# MAX86176_WRIST_EVKIT_D.net
KiCad netlist of a schematic drawn in EAGLE
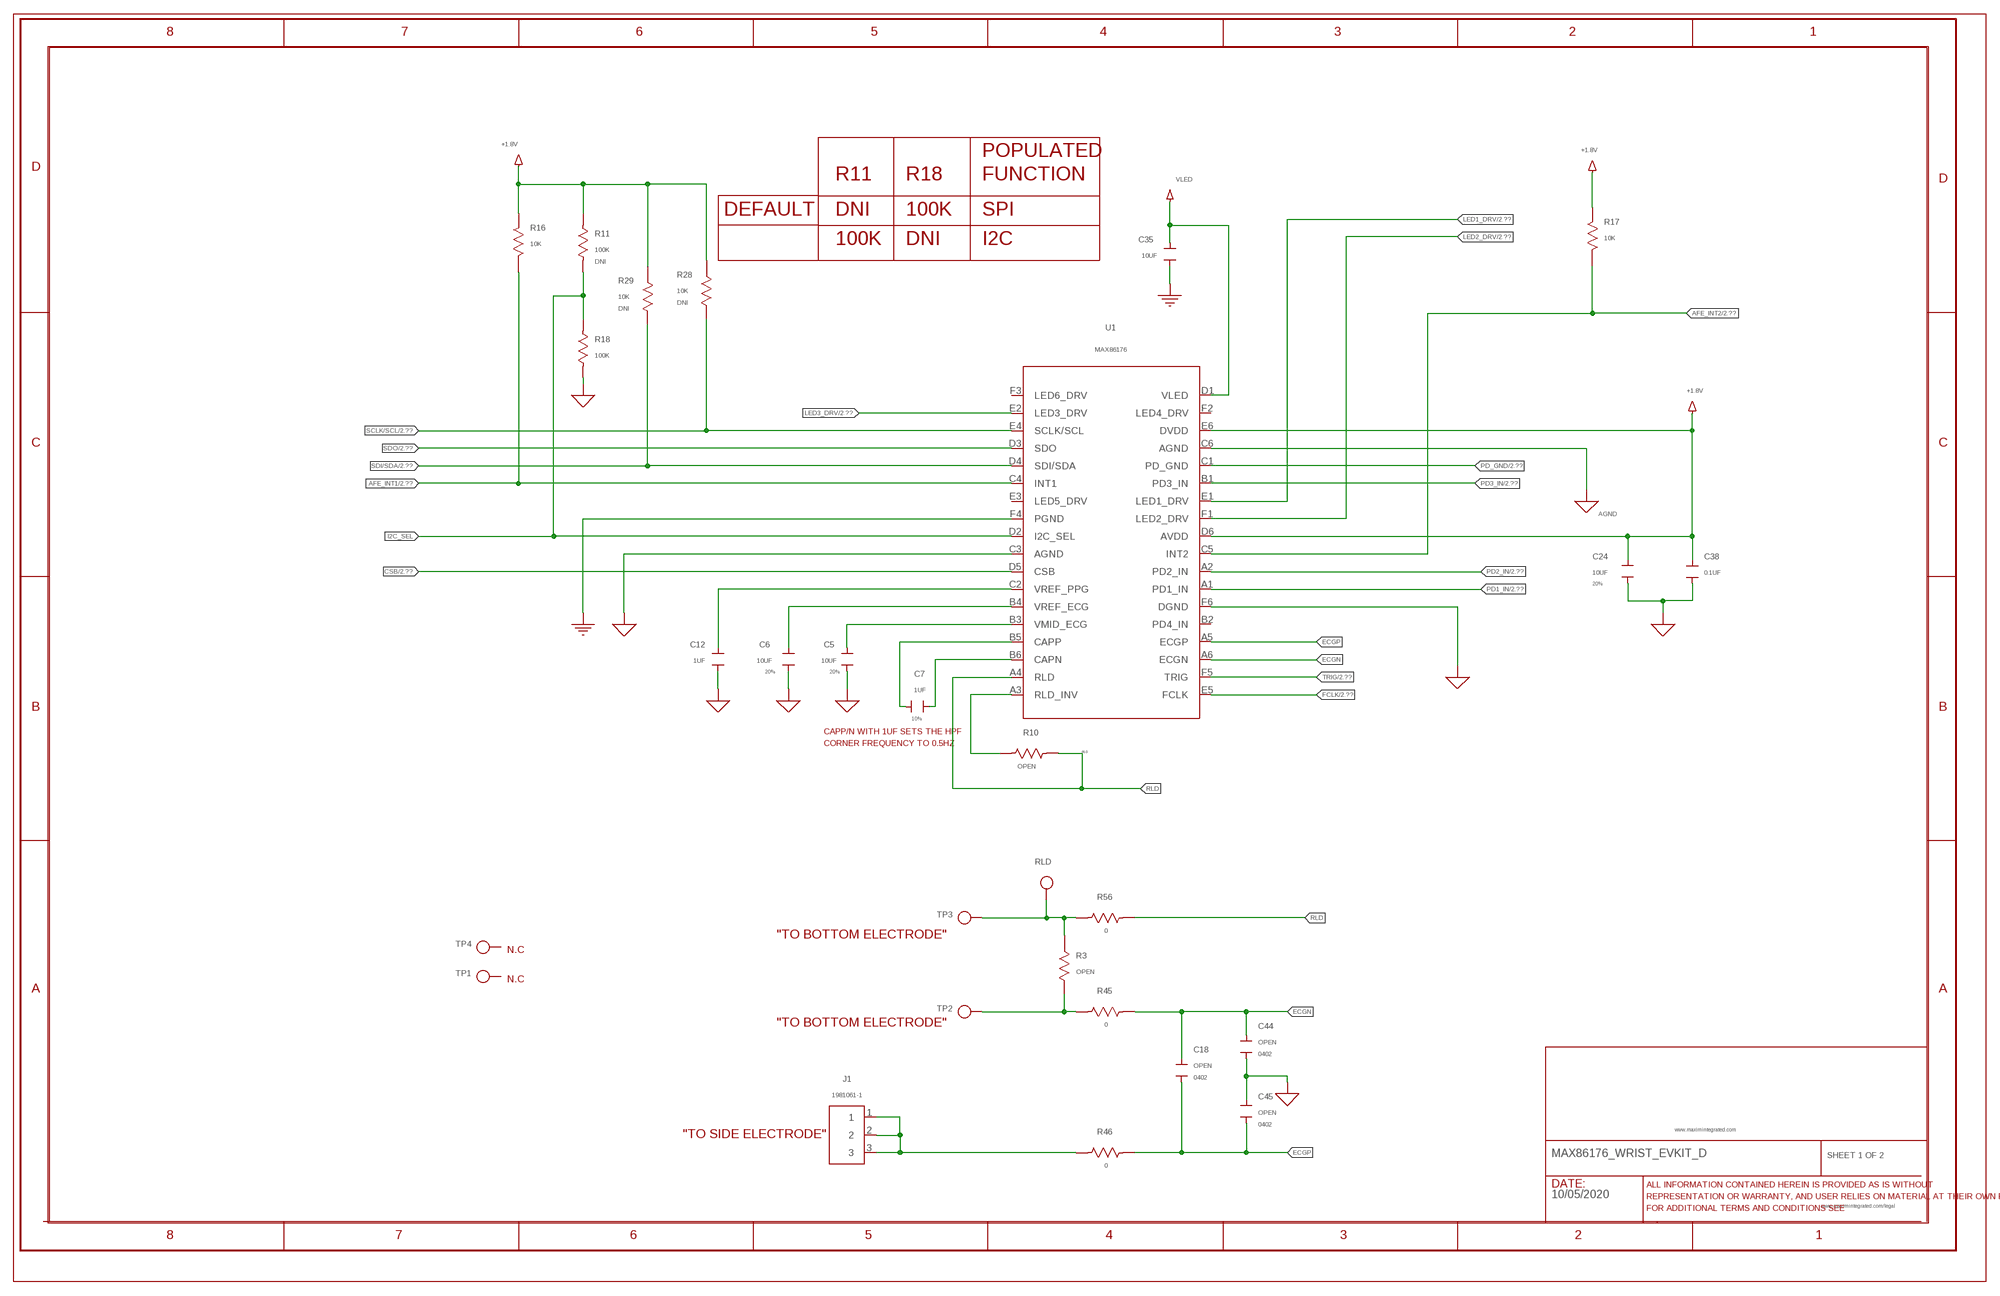
[diagram p0: schematic, sheet 1]
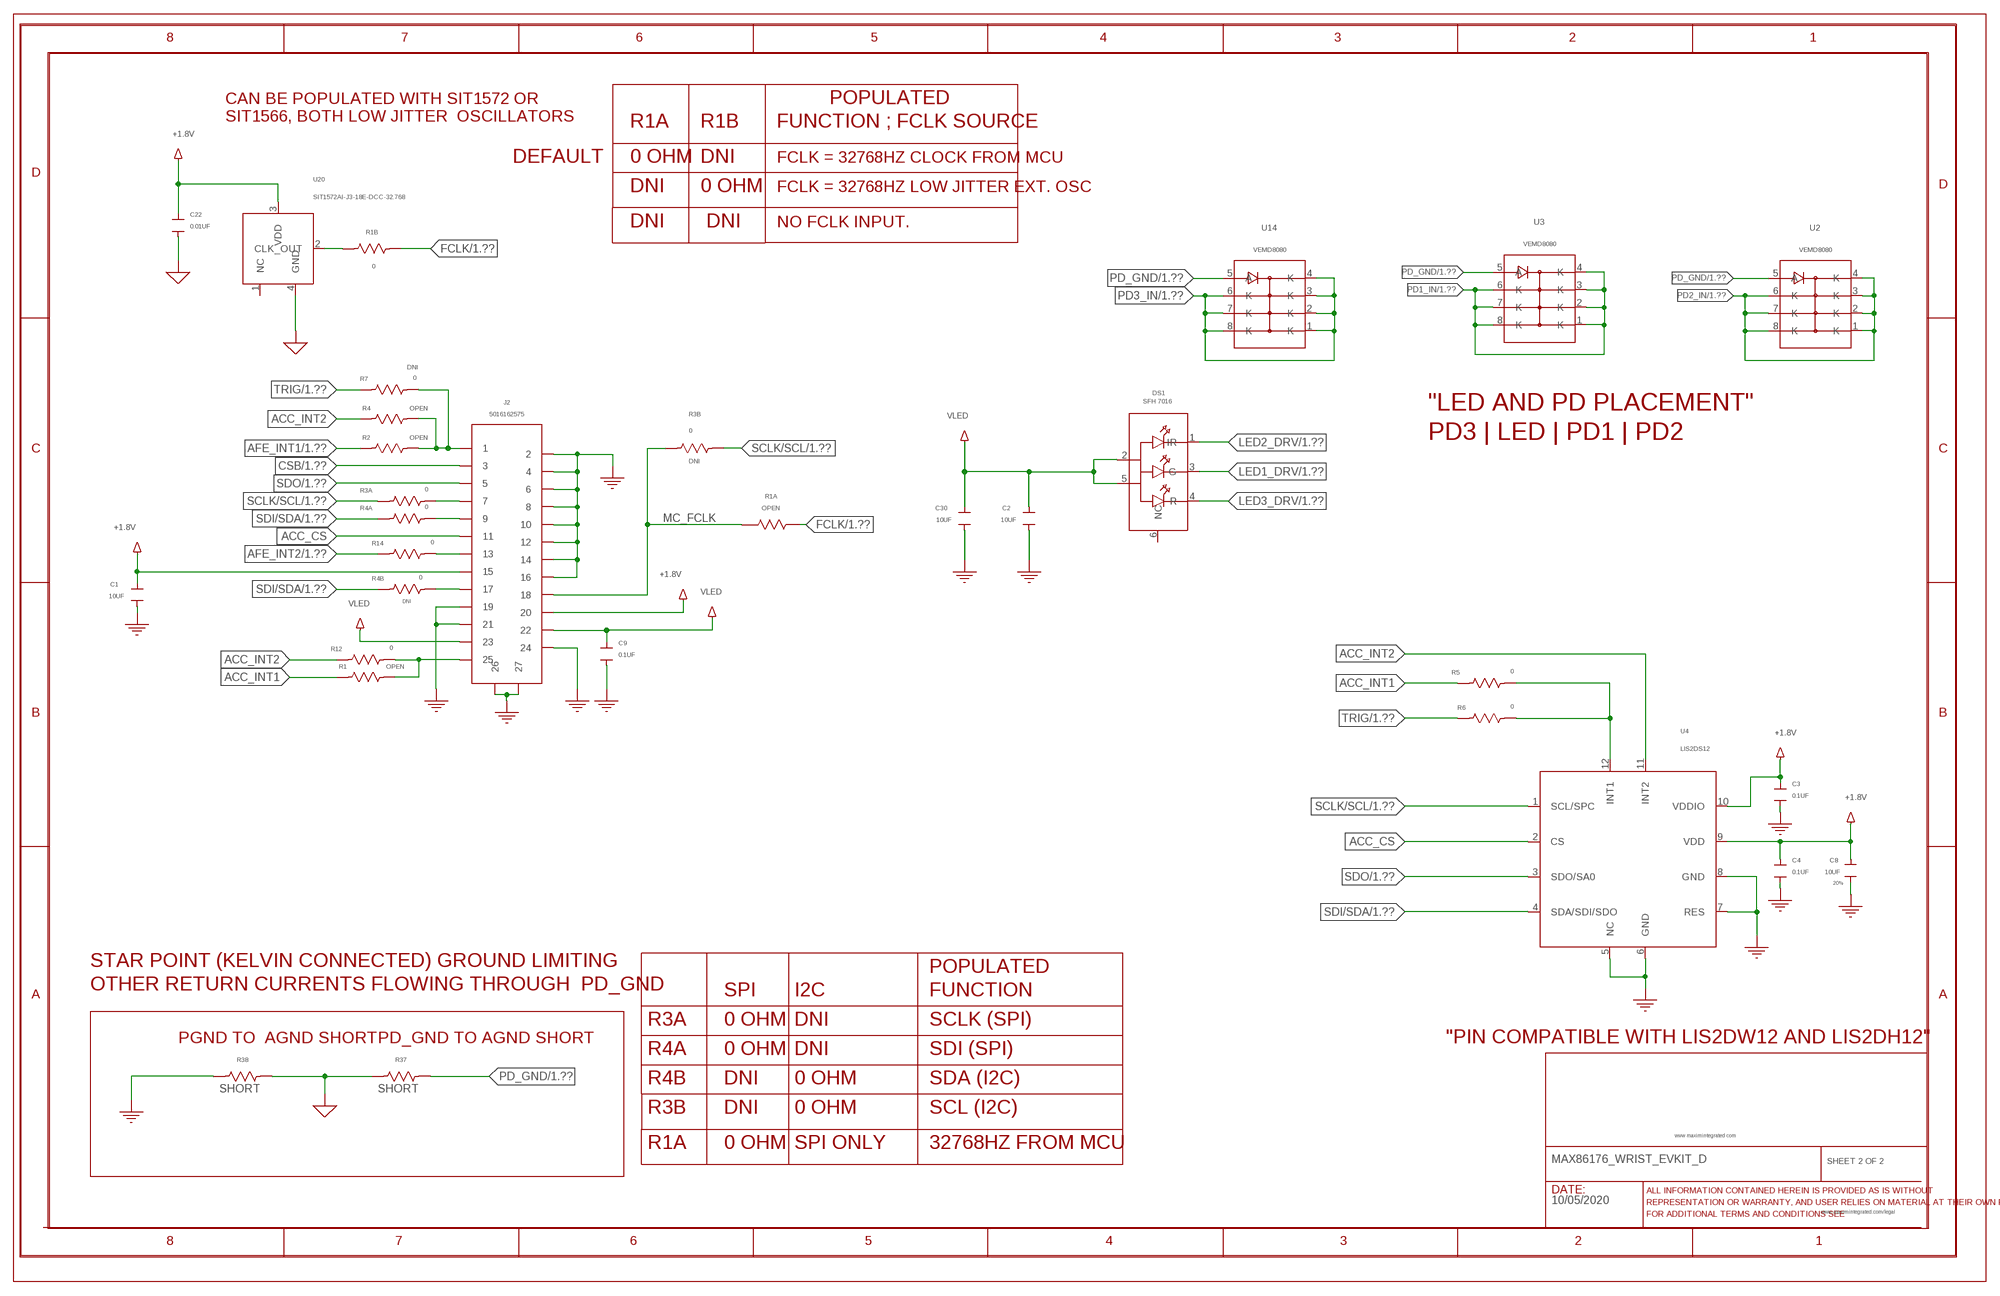
[diagram p1: schematic, sheet 2]

(export (version "E")
  (design (tool "Eeschema 10.0.6"))
  (components
    (comp (ref "C5")
      (value "10UF")
      (footprint "eagle-import:0402")
      (description "CAP: SMT (0402): 10UF: 20%: 10V: X5R: CERAMIC")
      (fields
        (field (name "CAP") "1.00E-05")
        (field (name "CASE") "SMT (0402)")
        (field (name "MANUFACTURER") "MURATA:MURATA:AVX:SAMSUNG")
        (field (name "MATERIAL_TYPE") "CERAMIC CHIP")
        (field (name "MAXINV") "20-0010U-BA12")
        (field (name "MFG_PART_NUMBER") "GRM155R61A106ME44:GRM155R61A106ME11:0402ZD106MAT2A:CL05A106MP5NUNC")
        (field (name "ORIGINALSYMBOLORIGIN") "(-50,50)")
        (field (name "PACK_TYPE") "0402CAP")
        (field (name "PHYS_PAGE") "1")
        (field (name "REFLOW") "-")
        (field (name "TEMP_RANGE") "-55 DEGC TO +85 DEGC")
        (field (name "TOLERANCE") "20%")
        (field (name "VER") "1")
        (field (name "VLOG_PARAM01") "CAP:INTEGER")
        (field (name "VOLTAGE_RATING") "10V")
      )
      (libsource (lib "eagle-import") (part "CAP_NP#1CAP_NP#1_1"))
    )
    (comp (ref "C6")
      (value "10UF")
      (footprint "eagle-import:0402")
      (description "CAP: SMT (0402): 10UF: 20%: 10V: X5R: CERAMIC")
      (fields
        (field (name "CAP") "1.00E-05")
        (field (name "CASE") "SMT (0402)")
        (field (name "MANUFACTURER") "MURATA:MURATA:AVX:SAMSUNG")
        (field (name "MATERIAL_TYPE") "CERAMIC CHIP")
        (field (name "MAXINV") "20-0010U-BA12")
        (field (name "MFG_PART_NUMBER") "GRM155R61A106ME44:GRM155R61A106ME11:0402ZD106MAT2A:CL05A106MP5NUNC")
        (field (name "ORIGINALSYMBOLORIGIN") "(-50,50)")
        (field (name "PACK_TYPE") "0402CAP")
        (field (name "PHYS_PAGE") "1")
        (field (name "REFLOW") "-")
        (field (name "TEMP_RANGE") "-55 DEGC TO +85 DEGC")
        (field (name "TOLERANCE") "20%")
        (field (name "VER") "1")
        (field (name "VLOG_PARAM01") "CAP:INTEGER")
        (field (name "VOLTAGE_RATING") "10V")
      )
      (libsource (lib "eagle-import") (part "CAP_NP#1CAP_NP#1_1"))
    )
    (comp (ref "C7")
      (value "1UF")
      (footprint "eagle-import:0603")
      (description "CAP: SMT (0603): 1UF: 10%: 25V: X7R: CERAMIC")
      (fields
        (field (name "CAP") "1.00E-06")
        (field (name "CASE") "SMT (0603)")
        (field (name "MANUFACTURER") "MURATA:TAIYO YUDEN:AVX:TAIYO YUDEN")
        (field (name "MATERIAL_TYPE") "CERAMIC CHIP")
        (field (name "MAXINV") "20-0001U-P6")
        (field (name "MFG_PART_NUMBER") "GRM188R71E105KA12:CGA3E1X7R1E105K:TMK107B7105KA:06033C105KAT2A:GCM188R71E105KA64:C1608X7R1E105K080AE:CGA3E1X7R1E105K080AC")
        (field (name "ORIGINALSYMBOLORIGIN") "(-50,50)")
        (field (name "PACK_TYPE") "0603CAP")
        (field (name "PHYS_PAGE") "1")
        (field (name "REFLOW") "-")
        (field (name "TEMP_RANGE") "-55 DEGC TO +125 DEGC")
        (field (name "TOLERANCE") "10%")
        (field (name "VER") "1")
        (field (name "VLOG_PARAM01") "CAP:INTEGER")
        (field (name "VOLTAGE_RATING") "25V")
      )
      (libsource (lib "eagle-import") (part "CAP_NP#1CAP_NP#1"))
    )
    (comp (ref "C12")
      (value "1UF")
      (footprint "eagle-import:0402")
      (description "CAP: SMT (0402): 1UF: 10%: 16V: X5R: CERAMIC")
      (fields
        (field (name "CAP") "1.00E-06")
        (field (name "CASE") "SMT (0402)")
        (field (name "MANUFACTURER") "SAMSUNG")
        (field (name "MATERIAL_TYPE") "CERAMIC CHIP")
        (field (name "MAXINV") "EC2430")
        (field (name "MFG_PART_NUMBER") "CL05A105KO5NNN")
        (field (name "ORIGINALSYMBOLORIGIN") "(-50,50)")
        (field (name "PACK_TYPE") "0402CAP")
        (field (name "PHYS_PAGE") "1")
        (field (name "REFLOW") "-")
        (field (name "TEMP_RANGE") "-55 DEGC TO +85 DEGC")
        (field (name "TOLERANCE") "10%")
        (field (name "VER") "2")
        (field (name "VLOG_PARAM01") "CAP:INTEGER")
        (field (name "VOLTAGE_RATING") "16V")
      )
      (libsource (lib "eagle-import") (part "CAP_NPCAP_NP_1"))
    )
    (comp (ref "C18")
      (value "OPEN")
      (footprint "eagle-import:0402")
      (description "PACKAGE OUTLINE 0402 NON-POLAR CAPACITOR - EVKIT")
      (fields
        (field (name "CASE") "N/A")
        (field (name "MANUFACTURER") "N/A")
        (field (name "MATERIAL_TYPE") "N/A")
        (field (name "MAXINV") "N/A")
        (field (name "MFG_PART_NUMBER") "N/A")
        (field (name "ORIGINALSYMBOLORIGIN") "(-50,50)")
        (field (name "PACK_TYPE") "0402CAP")
        (field (name "PHYS_PAGE") "1")
        (field (name "TEMP_RANGE") "N/A")
        (field (name "TOLERANCE") "N/A")
        (field (name "VER") "1")
        (field (name "VOLTAGE_RATING") "N/A")
      )
      (libsource (lib "eagle-import") (part "EVK_GENERIC_CAPACITORS"))
    )
    (comp (ref "C24")
      (value "10UF")
      (footprint "eagle-import:0603")
      (description "CAP: SMT (0603): 10UF: 20%: 25V: X5R: CERAMIC CHIP")
      (fields
        (field (name "CAP") "1.00E-05")
        (field (name "CASE") "SMT (0603)")
        (field (name "MANUFACTURER") "MURATA")
        (field (name "MATERIAL_TYPE") "CERAMIC CHIP")
        (field (name "MAXINV") "20-0010U-P7")
        (field (name "MFG_PART_NUMBER") "GRM188R61E106MA73")
        (field (name "ORIGINALSYMBOLORIGIN") "(-50,50)")
        (field (name "PACK_TYPE") "0603")
        (field (name "PHYS_PAGE") "1")
        (field (name "REFLOW") "-")
        (field (name "TEMP_RANGE") "-55 DEGC TO +85 DEGC")
        (field (name "TOLERANCE") "20%")
        (field (name "VER") "1")
        (field (name "VLOG_PARAM01") "CAP:INTEGER")
        (field (name "VOLTAGE_RATING") "25V")
      )
      (libsource (lib "eagle-import") (part "EK_CAP_NP#1"))
    )
    (comp (ref "C35")
      (value "10UF")
      (footprint "eagle-import:0603")
      (description "CAP: SMT (0603): 10UF: 20%: 25V: X5R: CERAMIC CHIP")
      (fields
        (field (name "CAP") "1.00E-05")
        (field (name "CASE") "SMT (0603)")
        (field (name "MANUFACTURER") "MURATA")
        (field (name "MATERIAL_TYPE") "CERAMIC CHIP")
        (field (name "MAXINV") "20-0010U-P7")
        (field (name "MFG_PART_NUMBER") "GRM188R61E106MA73")
        (field (name "ORIGINALSYMBOLORIGIN") "(-50,50)")
        (field (name "PACK_TYPE") "0603")
        (field (name "PHYS_PAGE") "1")
        (field (name "REFLOW") "-")
        (field (name "TEMP_RANGE") "-55 DEGC TO +85 DEGC")
        (field (name "TOLERANCE") "20%")
        (field (name "VER") "2")
        (field (name "VLOG_PARAM01") "CAP:INTEGER")
        (field (name "VOLTAGE_RATING") "25V")
      )
      (libsource (lib "eagle-import") (part "EK_CAP_NP"))
    )
    (comp (ref "C38")
      (value "0.1UF")
      (footprint "eagle-import:0603")
      (description "CAP: SMT (0603): 0.1UF: 10%: 100V: X7R: CERAMIC")
      (fields
        (field (name "CAP") "1.00E-07")
        (field (name "MANUFACTURER") "YAGEO:MURATA:TAIYO YUDEN:AVX:MURATA")
        (field (name "MAXINV") "20-000U1-01")
        (field (name "MFG_PART_NUMBER") "GRM188R72A104KA35: CC0603KRX7R0BB104")
        (field (name "ORIGINALSYMBOLORIGIN") "(-50,50)")
        (field (name "PACK_TYPE") "0603CAP")
        (field (name "PHYS_PAGE") "1")
        (field (name "REFLOW") "-")
        (field (name "TEMP_RANGE") "-55 DEGC TO +125 DEGC")
        (field (name "TOLERANCE") "10%")
        (field (name "VER") "2")
        (field (name "VLOG_PARAM01") "CAP:INTEGER")
        (field (name "VOLTAGE_RATING") "100V")
      )
      (libsource (lib "eagle-import") (part "CAP_NPCAP_NP_2"))
    )
    (comp (ref "C44")
      (value "OPEN")
      (footprint "eagle-import:0402")
      (description "PACKAGE OUTLINE 0402 NON-POLAR CAPACITOR - EVKIT")
      (fields
        (field (name "CASE") "N/A")
        (field (name "MANUFACTURER") "N/A")
        (field (name "MATERIAL_TYPE") "N/A")
        (field (name "MAXINV") "N/A")
        (field (name "MFG_PART_NUMBER") "N/A")
        (field (name "ORIGINALSYMBOLORIGIN") "(-50,50)")
        (field (name "PACK_TYPE") "0402CAP")
        (field (name "PHYS_PAGE") "1")
        (field (name "TEMP_RANGE") "N/A")
        (field (name "TOLERANCE") "N/A")
        (field (name "VER") "1")
        (field (name "VOLTAGE_RATING") "N/A")
      )
      (libsource (lib "eagle-import") (part "EVK_GENERIC_CAPACITORS"))
    )
    (comp (ref "C45")
      (value "OPEN")
      (footprint "eagle-import:0402")
      (description "PACKAGE OUTLINE 0402 NON-POLAR CAPACITOR - EVKIT")
      (fields
        (field (name "CASE") "N/A")
        (field (name "MANUFACTURER") "N/A")
        (field (name "MATERIAL_TYPE") "N/A")
        (field (name "MAXINV") "N/A")
        (field (name "MFG_PART_NUMBER") "N/A")
        (field (name "ORIGINALSYMBOLORIGIN") "(-50,50)")
        (field (name "PACK_TYPE") "0402CAP")
        (field (name "PHYS_PAGE") "1")
        (field (name "TEMP_RANGE") "N/A")
        (field (name "TOLERANCE") "N/A")
        (field (name "VER") "1")
        (field (name "VOLTAGE_RATING") "N/A")
      )
      (libsource (lib "eagle-import") (part "EVK_GENERIC_CAPACITORS"))
    )
    (comp (ref "J1")
      (value "1981061-1")
      (footprint "eagle-import:TECO_1981061-1")
      (description "CONNECTOR: MALE: SMD: LEAF TYPE BATTERY CONNECTOR: WITHOUT BOSS: 3 PINS")
      (fields
        (field (name "MANUFACTURER") "TYCO")
        (field (name "MAXINV") "EH111000003993")
        (field (name "MFG_PART_NUMBER") "1981061-1")
        (field (name "ORIGINALSYMBOLORIGIN") "(-75,125)")
        (field (name "PACK_TYPE") "SMD")
        (field (name "PHYS_PAGE") "1")
        (field (name "REFLOW") "-")
        (field (name "TEMP_RANGE") "N/A")
        (field (name "TOLERANCE") "N/A")
        (field (name "VER") "1")
        (field (name "VOLTAGE_RATING") "N/A")
      )
      (libsource (lib "eagle-import") (part "1981061-1"))
    )
    (comp (ref "R3")
      (value "OPEN")
      (footprint "eagle-import:RESC0603X33M")
      (description "PACKAGE OUTLINE 0201 RESISTOR - EVKIT")
      (fields
        (field (name "CASE") "SMT (0201)")
        (field (name "MANUFACTURER") "N/A")
        (field (name "MATERIAL_TYPE") "N/A")
        (field (name "MAXINV") "N/A")
        (field (name "MFG_PART_NUMBER") "N/A")
        (field (name "ORIGINALSYMBOLORIGIN") "(-50,75)")
        (field (name "PACK_TYPE") "0201RES")
        (field (name "PHYS_PAGE") "1")
        (field (name "POWER_RATING") "N/A")
        (field (name "TEMP_RANGE") "N/A")
        (field (name "TOLERANCE") "N/A")
        (field (name "VER") "4")
        (field (name "VOLTAGE_RATING") "N/A")
      )
      (libsource (lib "eagle-import") (part "EVK_GENERIC_RESISTORS#1"))
    )
    (comp (ref "R10")
      (value "OPEN")
      (footprint "eagle-import:0402")
      (description "PACKAGE OUTLINE 0402 RESISTOR - EVKIT")
      (fields
        (field (name "CASE") "SMT (0402)")
        (field (name "MANUFACTURER") "N/A")
        (field (name "MATERIAL_TYPE") "N/A")
        (field (name "MAXINV") "N/A")
        (field (name "MFG_PART_NUMBER") "N/A")
        (field (name "ORIGINALSYMBOLORIGIN") "(-75,50)")
        (field (name "PACK_TYPE") "0402RES")
        (field (name "PHYS_PAGE") "1")
        (field (name "POWER_RATING") "N/A")
        (field (name "TEMP_RANGE") "N/A")
        (field (name "TOLERANCE") "N/A")
        (field (name "VER") "2")
        (field (name "VOLTAGE_RATING") "N/A")
      )
      (libsource (lib "eagle-import") (part "EVK_GENERIC_RESISTORSEVK_GENERIC_RESISTORS_1"))
    )
    (comp (ref "R11")
      (value "100K")
      (footprint "eagle-import:0402")
      (description "RES: SMT (0402): 100K: 1%: +/-100PPM/DEGC: 0.1000W")
      (fields
        (field (name "CASE") "SMT (0402)")
        (field (name "MANUFACTURER") "PANASONIC")
        (field (name "MATERIAL_TYPE") "THICK FILM")
        (field (name "MAXINV") "80-0100K-18")
        (field (name "MFG_PART_NUMBER") "ERJ-2RKF1003")
        (field (name "ORIGINALSYMBOLORIGIN") "(-75,50)")
        (field (name "PACK_TYPE") "0402RES")
        (field (name "PHYS_PAGE") "1")
        (field (name "POWER_RATING") "0.10W")
        (field (name "REFLOW") "-")
        (field (name "RES") "1.00E05")
        (field (name "TEMP_RANGE") "-55 DEGC TO +155 DEGC")
        (field (name "TOLERANCE") "1%")
        (field (name "VARIANT") "DNI")
        (field (name "VER") "2")
        (field (name "VLOG_PARAM01") "RES:INTEGER")
      )
      (libsource (lib "eagle-import") (part "RES_SMD#1RES_SMD#1_1"))
    )
    (comp (ref "R16")
      (value "10K")
      (footprint "eagle-import:0402")
      (description "RES: SMT (0402): 10K: 1%: +/-100PPM/DEGC: 0.1000W")
      (fields
        (field (name "CASE") "SMT (0402)")
        (field (name "MANUFACTURER") "PANASONIC")
        (field (name "MATERIAL_TYPE") "THICK FILM")
        (field (name "MAXINV") "80-0010K-18")
        (field (name "MFG_PART_NUMBER") "ERJ-2RKF1002")
        (field (name "ORIGINALSYMBOLORIGIN") "(-50,75)")
        (field (name "PACK_TYPE") "0402RES")
        (field (name "PHYS_PAGE") "1")
        (field (name "POWER_RATING") "0.10W")
        (field (name "REFLOW") "-")
        (field (name "RES") "1.00E04")
        (field (name "TEMP_RANGE") "-55 DEGC TO +155 DEGC")
        (field (name "TOLERANCE") "1%")
        (field (name "VER") "4")
        (field (name "VLOG_PARAM01") "RES:INTEGER")
      )
      (libsource (lib "eagle-import") (part "RES_SMD"))
    )
    (comp (ref "R17")
      (value "10K")
      (footprint "eagle-import:0402")
      (description "RES: SMT (0402): 10K: 1%: +/-100PPM/DEGC: 0.1000W")
      (fields
        (field (name "CASE") "SMT (0402)")
        (field (name "MANUFACTURER") "PANASONIC")
        (field (name "MATERIAL_TYPE") "THICK FILM")
        (field (name "MAXINV") "80-0010K-18")
        (field (name "MFG_PART_NUMBER") "ERJ-2RKF1002")
        (field (name "ORIGINALSYMBOLORIGIN") "(-50,75)")
        (field (name "PACK_TYPE") "0402RES")
        (field (name "PHYS_PAGE") "1")
        (field (name "POWER_RATING") "0.10W")
        (field (name "REFLOW") "-")
        (field (name "RES") "1.00E04")
        (field (name "TEMP_RANGE") "-55 DEGC TO +155 DEGC")
        (field (name "TOLERANCE") "1%")
        (field (name "VER") "4")
        (field (name "VLOG_PARAM01") "RES:INTEGER")
      )
      (libsource (lib "eagle-import") (part "RES_SMD"))
    )
    (comp (ref "R18")
      (value "100K")
      (footprint "eagle-import:0402")
      (description "RES: SMT (0402): 100K: 1%: +/-100PPM/DEGC: 0.1000W")
      (fields
        (field (name "CASE") "SMT (0402)")
        (field (name "MANUFACTURER") "PANASONIC")
        (field (name "MATERIAL_TYPE") "THICK FILM")
        (field (name "MAXINV") "80-0100K-18")
        (field (name "MFG_PART_NUMBER") "ERJ-2RKF1003")
        (field (name "ORIGINALSYMBOLORIGIN") "(-75,50)")
        (field (name "PACK_TYPE") "0402RES")
        (field (name "PHYS_PAGE") "1")
        (field (name "POWER_RATING") "0.10W")
        (field (name "REFLOW") "-")
        (field (name "RES") "1.00E05")
        (field (name "TEMP_RANGE") "-55 DEGC TO +155 DEGC")
        (field (name "TOLERANCE") "1%")
        (field (name "VER") "2")
        (field (name "VLOG_PARAM01") "RES:INTEGER")
      )
      (libsource (lib "eagle-import") (part "RES_SMD#1RES_SMD#1_1"))
    )
    (comp (ref "R28")
      (value "10K")
      (footprint "eagle-import:0402")
      (description "RES: SMT (0402): 10K: 1%: +/-100PPM/DEGC: 0.1000W")
      (fields
        (field (name "CASE") "SMT (0402)")
        (field (name "MANUFACTURER") "PANASONIC")
        (field (name "MATERIAL_TYPE") "THICK FILM")
        (field (name "MAXINV") "80-0010K-18")
        (field (name "MFG_PART_NUMBER") "ERJ-2RKF1002")
        (field (name "ORIGINALSYMBOLORIGIN") "(-50,75)")
        (field (name "PACK_TYPE") "0402RES")
        (field (name "PHYS_PAGE") "1")
        (field (name "POWER_RATING") "0.10W")
        (field (name "REFLOW") "-")
        (field (name "RES") "1.00E04")
        (field (name "TEMP_RANGE") "-55 DEGC TO +155 DEGC")
        (field (name "TOLERANCE") "1%")
        (field (name "VARIANT") "DNI")
        (field (name "VER") "4")
        (field (name "VLOG_PARAM01") "RES:INTEGER")
      )
      (libsource (lib "eagle-import") (part "RES_SMD"))
    )
    (comp (ref "R29")
      (value "10K")
      (footprint "eagle-import:0402")
      (description "RES: SMT (0402): 10K: 1%: +/-100PPM/DEGC: 0.1000W")
      (fields
        (field (name "CASE") "SMT (0402)")
        (field (name "MANUFACTURER") "PANASONIC")
        (field (name "MATERIAL_TYPE") "THICK FILM")
        (field (name "MAXINV") "80-0010K-18")
        (field (name "MFG_PART_NUMBER") "ERJ-2RKF1002")
        (field (name "ORIGINALSYMBOLORIGIN") "(-50,75)")
        (field (name "PACK_TYPE") "0402RES")
        (field (name "PHYS_PAGE") "1")
        (field (name "POWER_RATING") "0.10W")
        (field (name "REFLOW") "-")
        (field (name "RES") "1.00E04")
        (field (name "TEMP_RANGE") "-55 DEGC TO +155 DEGC")
        (field (name "TOLERANCE") "1%")
        (field (name "VARIANT") "DNI")
        (field (name "VER") "4")
        (field (name "VLOG_PARAM01") "RES:INTEGER")
      )
      (libsource (lib "eagle-import") (part "RES_SMD"))
    )
    (comp (ref "R45")
      (value "0")
      (footprint "eagle-import:0402")
      (description "RES: SMT (0402): 0: JUMPER: JUMPER: 0.1000W")
      (fields
        (field (name "CASE") "SMT (0402)")
        (field (name "MANUFACTURER") "PANASONIC")
        (field (name "MATERIAL_TYPE") "THICK FILM")
        (field (name "MAXINV") "80-0000R-26A")
        (field (name "MFG_PART_NUMBER") "ERJ-2GE0R00")
        (field (name "ORIGINALSYMBOLORIGIN") "(-75,50)")
        (field (name "PACK_TYPE") "0402RES")
        (field (name "PHYS_PAGE") "1")
        (field (name "POWER_RATING") "0.10W")
        (field (name "REFLOW") "-")
        (field (name "RES") "0.00000001E00")
        (field (name "TEMP_RANGE") "-55 DEGC TO +155 DEGC")
        (field (name "TOLERANCE") "0%")
        (field (name "VER") "2")
        (field (name "VLOG_PARAM01") "RES:INTEGER")
      )
      (libsource (lib "eagle-import") (part "RES_SMD#1RES_SMD#1_1"))
    )
    (comp (ref "R46")
      (value "0")
      (footprint "eagle-import:0402")
      (description "RES: SMT (0402): 0: JUMPER: JUMPER: 0.1000W")
      (fields
        (field (name "CASE") "SMT (0402)")
        (field (name "MANUFACTURER") "PANASONIC")
        (field (name "MATERIAL_TYPE") "THICK FILM")
        (field (name "MAXINV") "80-0000R-26A")
        (field (name "MFG_PART_NUMBER") "ERJ-2GE0R00")
        (field (name "ORIGINALSYMBOLORIGIN") "(-75,50)")
        (field (name "PACK_TYPE") "0402RES")
        (field (name "PHYS_PAGE") "1")
        (field (name "POWER_RATING") "0.10W")
        (field (name "REFLOW") "-")
        (field (name "RES") "0.00000001E00")
        (field (name "TEMP_RANGE") "-55 DEGC TO +155 DEGC")
        (field (name "TOLERANCE") "0%")
        (field (name "VER") "2")
        (field (name "VLOG_PARAM01") "RES:INTEGER")
      )
      (libsource (lib "eagle-import") (part "RES_SMD#1RES_SMD#1_1"))
    )
    (comp (ref "R56")
      (value "0")
      (footprint "eagle-import:0402")
      (description "RES: SMT (0402): 0: JUMPER: JUMPER: 0.1000W")
      (fields
        (field (name "CASE") "SMT (0402)")
        (field (name "MANUFACTURER") "PANASONIC")
        (field (name "MATERIAL_TYPE") "THICK FILM")
        (field (name "MAXINV") "80-0000R-26A")
        (field (name "MFG_PART_NUMBER") "ERJ-2GE0R00")
        (field (name "ORIGINALSYMBOLORIGIN") "(-75,50)")
        (field (name "PACK_TYPE") "0402RES")
        (field (name "PHYS_PAGE") "1")
        (field (name "POWER_RATING") "0.10W")
        (field (name "REFLOW") "-")
        (field (name "RES") "0.00000001E00")
        (field (name "TEMP_RANGE") "-55 DEGC TO +155 DEGC")
        (field (name "TOLERANCE") "0%")
        (field (name "VER") "2")
        (field (name "VLOG_PARAM01") "RES:INTEGER")
      )
      (libsource (lib "eagle-import") (part "RES_SMD#1RES_SMD#1_1"))
    )
    (comp (ref "RLD")
      (value "N/A")
      (footprint "eagle-import:TP_C25H12")
      (description "TESTPOINT WITH 12 MILS HOLE DIA, and 25 MILS PAD DIA: NOT FOR COLD TEST")
      (fields
        (field (name "MANUFACTURER") "N/A")
        (field (name "MAXINV") "N/A")
        (field (name "MFG_PART_NUMBER") "N/A")
        (field (name "ORIGINALSYMBOLORIGIN") "(-125,50)")
        (field (name "PACK_TYPE") "TP")
        (field (name "PART_NAME") "TP")
        (field (name "PHYS_PAGE") "1")
        (field (name "REFLOW") "-")
        (field (name "TEMP_RANGE") "N/A")
        (field (name "TOLERANCE") "N/A")
        (field (name "VER") "1")
        (field (name "VOLTAGE_RATING") "N/A")
      )
      (libsource (lib "eagle-import") (part "TPTP"))
    )
    (comp (ref "TP1")
      (value "N/A")
      (footprint "eagle-import:TP_S_SQUARE_3-50")
      (description "TESTPOINT WITH 3.50MM SQUARE PAD DIAMETER")
      (fields
        (field (name "MANUFACTURER") "N/A")
        (field (name "MAXINV") "N/A")
        (field (name "MFG_PART_NUMBER") "N/A")
        (field (name "ORIGINALSYMBOLORIGIN") "(-125,50)")
        (field (name "PACK_TYPE") "TP")
        (field (name "PART_NAME") "TP")
        (field (name "PHYS_PAGE") "1")
        (field (name "REFLOW") "-")
        (field (name "TEMP_RANGE") "N/A")
        (field (name "TOLERANCE") "N/A")
        (field (name "VER") "1")
        (field (name "VOLTAGE_RATING") "N/A")
      )
      (libsource (lib "eagle-import") (part "TPTP_1"))
    )
    (comp (ref "TP2")
      (value "N/A")
      (footprint "eagle-import:TP_S_SQUARE_3-50")
      (description "TESTPOINT WITH 3.50MM SQUARE PAD DIAMETER")
      (fields
        (field (name "MANUFACTURER") "N/A")
        (field (name "MAXINV") "N/A")
        (field (name "MFG_PART_NUMBER") "N/A")
        (field (name "ORIGINALSYMBOLORIGIN") "(-125,50)")
        (field (name "PACK_TYPE") "TP")
        (field (name "PART_NAME") "TP")
        (field (name "PHYS_PAGE") "1")
        (field (name "REFLOW") "-")
        (field (name "TEMP_RANGE") "N/A")
        (field (name "TOLERANCE") "N/A")
        (field (name "VER") "1")
        (field (name "VOLTAGE_RATING") "N/A")
      )
      (libsource (lib "eagle-import") (part "TPTP_1"))
    )
    (comp (ref "TP3")
      (value "N/A")
      (footprint "eagle-import:TP_S_SQUARE_3-50")
      (description "TESTPOINT WITH 3.50MM SQUARE PAD DIAMETER")
      (fields
        (field (name "MANUFACTURER") "N/A")
        (field (name "MAXINV") "N/A")
        (field (name "MFG_PART_NUMBER") "N/A")
        (field (name "ORIGINALSYMBOLORIGIN") "(-125,50)")
        (field (name "PACK_TYPE") "TP")
        (field (name "PART_NAME") "TP")
        (field (name "PHYS_PAGE") "1")
        (field (name "REFLOW") "-")
        (field (name "TEMP_RANGE") "N/A")
        (field (name "TOLERANCE") "N/A")
        (field (name "VER") "1")
        (field (name "VOLTAGE_RATING") "N/A")
      )
      (libsource (lib "eagle-import") (part "TPTP_1"))
    )
    (comp (ref "TP4")
      (value "N/A")
      (footprint "eagle-import:TP_S_SQUARE_3-50")
      (description "TESTPOINT WITH 3.50MM SQUARE PAD DIAMETER")
      (fields
        (field (name "MANUFACTURER") "N/A")
        (field (name "MAXINV") "N/A")
        (field (name "MFG_PART_NUMBER") "N/A")
        (field (name "ORIGINALSYMBOLORIGIN") "(-125,50)")
        (field (name "PACK_TYPE") "TP")
        (field (name "PART_NAME") "TP")
        (field (name "PHYS_PAGE") "1")
        (field (name "REFLOW") "-")
        (field (name "TEMP_RANGE") "N/A")
        (field (name "TOLERANCE") "N/A")
        (field (name "VER") "1")
        (field (name "VOLTAGE_RATING") "N/A")
      )
      (libsource (lib "eagle-import") (part "TPTP_1"))
    )
    (comp (ref "U1")
      (value "MAX86176")
      (footprint "eagle-import:MAXIM_21-100413")
      (description "EVKIT PART - IC: MAX86176: ULTRA-LOW POWER: OPTICAL PPG AND SINGLE LEAD ECD AFE: PACKAGE OUTLINE DRAWING: 21-100413: PACKAGE CODE: N362D2+1")
      (fields
        (field (name "MANUFACTURER") "MAXIM")
        (field (name "MAXINV") "N/A")
        (field (name "MFG_PART_NUMBER") "MAX86176")
        (field (name "ORIGINALSYMBOLORIGIN") "(-375,775)")
        (field (name "PACK_TYPE") "WLP36_1")
        (field (name "PHYS_PAGE") "1")
        (field (name "REFLOW") "-")
        (field (name "SEC_TYPE") "WLP36_1")
        (field (name "TEMP_RANGE") "-40 DEGC TO +85 DEGC")
        (field (name "TOLERANCE") "N/A")
        (field (name "VER") "5")
        (field (name "VOLTAGE_RATING") "+1.7V TO +2V")
      )
      (libsource (lib "eagle-import") (part "EK_MAX86176"))
    )
    (comp (ref "C1")
      (value "10UF")
      (footprint "eagle-import:0603")
      (description "CAP: SMT (0603): 10UF: 20%: 25V: X5R: CERAMIC CHIP")
      (fields
        (field (name "CAP") "1.00E-05")
        (field (name "CASE") "SMT (0603)")
        (field (name "MANUFACTURER") "MURATA")
        (field (name "MATERIAL_TYPE") "CERAMIC CHIP")
        (field (name "MAXINV") "20-0010U-P7")
        (field (name "MFG_PART_NUMBER") "GRM188R61E106MA73")
        (field (name "ORIGINALSYMBOLORIGIN") "(-50,50)")
        (field (name "PACK_TYPE") "0603")
        (field (name "PHYS_PAGE") "2")
        (field (name "REFLOW") "-")
        (field (name "TEMP_RANGE") "-55 DEGC TO +85 DEGC")
        (field (name "TOLERANCE") "20%")
        (field (name "VER") "2")
        (field (name "VLOG_PARAM01") "CAP:INTEGER")
        (field (name "VOLTAGE_RATING") "25V")
      )
      (libsource (lib "eagle-import") (part "EK_CAP_NP"))
    )
    (comp (ref "C2")
      (value "10UF")
      (footprint "eagle-import:0603")
      (description "CAP: SMT (0603): 10UF: 20%: 25V: X5R: CERAMIC CHIP")
      (fields
        (field (name "CAP") "1.00E-05")
        (field (name "CASE") "SMT (0603)")
        (field (name "MANUFACTURER") "MURATA")
        (field (name "MATERIAL_TYPE") "CERAMIC CHIP")
        (field (name "MAXINV") "20-0010U-P7")
        (field (name "MFG_PART_NUMBER") "GRM188R61E106MA73")
        (field (name "ORIGINALSYMBOLORIGIN") "(-50,50)")
        (field (name "PACK_TYPE") "0603")
        (field (name "PHYS_PAGE") "2")
        (field (name "REFLOW") "-")
        (field (name "TEMP_RANGE") "-55 DEGC TO +85 DEGC")
        (field (name "TOLERANCE") "20%")
        (field (name "VER") "2")
        (field (name "VLOG_PARAM01") "CAP:INTEGER")
        (field (name "VOLTAGE_RATING") "25V")
      )
      (libsource (lib "eagle-import") (part "EK_CAP_NP"))
    )
    (comp (ref "C3")
      (value "0.1UF")
      (footprint "eagle-import:0603")
      (description "CAP: SMT (0603): 0.1UF: 10%: 100V: X7R: CERAMIC")
      (fields
        (field (name "CAP") "1.00E-07")
        (field (name "MANUFACTURER") "YAGEO:MURATA:TAIYO YUDEN:AVX:MURATA")
        (field (name "MAXINV") "20-000U1-01")
        (field (name "MFG_PART_NUMBER") "GRM188R72A104KA35: CC0603KRX7R0BB104")
        (field (name "ORIGINALSYMBOLORIGIN") "(-50,50)")
        (field (name "PACK_TYPE") "0603CAP")
        (field (name "PHYS_PAGE") "2")
        (field (name "REFLOW") "-")
        (field (name "TEMP_RANGE") "-55 DEGC TO +125 DEGC")
        (field (name "TOLERANCE") "10%")
        (field (name "VER") "2")
        (field (name "VLOG_PARAM01") "CAP:INTEGER")
        (field (name "VOLTAGE_RATING") "100V")
      )
      (libsource (lib "eagle-import") (part "CAP_NPCAP_NP_2"))
    )
    (comp (ref "C4")
      (value "0.1UF")
      (footprint "eagle-import:0603")
      (description "CAP: SMT (0603): 0.1UF: 10%: 100V: X7R: CERAMIC")
      (fields
        (field (name "CAP") "1.00E-07")
        (field (name "MANUFACTURER") "YAGEO:MURATA:TAIYO YUDEN:AVX:MURATA")
        (field (name "MAXINV") "20-000U1-01")
        (field (name "MFG_PART_NUMBER") "GRM188R72A104KA35: CC0603KRX7R0BB104")
        (field (name "ORIGINALSYMBOLORIGIN") "(-50,50)")
        (field (name "PACK_TYPE") "0603CAP")
        (field (name "PHYS_PAGE") "2")
        (field (name "REFLOW") "-")
        (field (name "TEMP_RANGE") "-55 DEGC TO +125 DEGC")
        (field (name "TOLERANCE") "10%")
        (field (name "VER") "2")
        (field (name "VLOG_PARAM01") "CAP:INTEGER")
        (field (name "VOLTAGE_RATING") "100V")
      )
      (libsource (lib "eagle-import") (part "CAP_NPCAP_NP_2"))
    )
    (comp (ref "C8")
      (value "10UF")
      (footprint "eagle-import:0402")
      (description "CAP: SMT (0402): 10UF: 20%: 10V: X5R: CERAMIC")
      (fields
        (field (name "CAP") "1.00E-05")
        (field (name "CASE") "SMT (0402)")
        (field (name "MANUFACTURER") "MURATA:MURATA:AVX:SAMSUNG")
        (field (name "MAXINV") "20-0010U-BA12")
        (field (name "MFG_PART_NUMBER") "GRM155R61A106ME44:GRM155R61A106ME11:0402ZD106MAT2A:CL05A106MP5NUNC")
        (field (name "ORIGINALSYMBOLORIGIN") "(-50,50)")
        (field (name "PACK_TYPE") "0402CAP")
        (field (name "PHYS_PAGE") "2")
        (field (name "REFLOW") "-")
        (field (name "TEMP_RANGE") "-55 DEGC TO +85 DEGC")
        (field (name "TOLERANCE") "20%")
        (field (name "VER") "1")
        (field (name "VLOG_PARAM01") "CAP:INTEGER")
        (field (name "VOLTAGE_RATING") "10V")
      )
      (libsource (lib "eagle-import") (part "CAP_NP#1CAP_NP#1_1"))
    )
    (comp (ref "C9")
      (value "0.1UF")
      (footprint "eagle-import:CAPC0603X33M")
      (description "CAP: SMT (0201): 0.1UF: 10%: 10V: X5R: CERAMIC")
      (fields
        (field (name "CAP") "1.00E-07")
        (field (name "CASE") "SMT (0201)")
        (field (name "MANUFACTURER") "MURATA:TAIYO YUDEN")
        (field (name "MATERIAL_TYPE") "CERAMIC")
        (field (name "MAXINV") "20-000U1-H9")
        (field (name "MFG_PART_NUMBER") "GRM033R61A104KE15: LMK063BJ104KP")
        (field (name "ORIGINALSYMBOLORIGIN") "(-50,50)")
        (field (name "PACK_TYPE") "0201CAPM")
        (field (name "PHYS_PAGE") "2")
        (field (name "REFLOW") "-")
        (field (name "TEMP_RANGE") "-55 DEGC TO +85 DEGC")
        (field (name "TOLERANCE") "N/A")
        (field (name "VER") "2")
        (field (name "VLOG_PARAM01") "CAP:INTEGER")
        (field (name "VOLTAGE_RATING") "10V")
      )
      (libsource (lib "eagle-import") (part "CAP_NPCAP_NP"))
    )
    (comp (ref "C22")
      (value "0.01UF")
      (footprint "eagle-import:CAPC0603X33M")
      (description "CAP: SMT (0201): 0.01UF: 10%: 10V: X7R: CERAMIC")
      (fields
        (field (name "CAP") "1.00E-08")
        (field (name "CASE") "SMT (0201)")
        (field (name "MANUFACTURER") "TDK:MURATA:MURATA:TDK:AVX")
        (field (name "MATERIAL_TYPE") "CERAMIC CHIP")
        (field (name "MAXINV") "20-00U01-I6")
        (field (name "MFG_PART_NUMBER") "C0603X7R1A103K030BA:GRM033R71A103KA01:GCM033R71A103KA03:CGA1A2X7R1A103K030BA:0201ZC103KAT2A")
        (field (name "ORIGINALSYMBOLORIGIN") "(-50,50)")
        (field (name "PACK_TYPE") "0201CAPM")
        (field (name "PHYS_PAGE") "2")
        (field (name "REFLOW") "-")
        (field (name "TEMP_RANGE") "-55 DEGC TO +125 DEGC")
        (field (name "TOLERANCE") "10%")
        (field (name "VER") "2")
        (field (name "VLOG_PARAM01") "CAP:INTEGER")
        (field (name "VOLTAGE_RATING") "10V")
      )
      (libsource (lib "eagle-import") (part "CAP_NPCAP_NP"))
    )
    (comp (ref "C30")
      (value "10UF")
      (footprint "eagle-import:0603")
      (description "CAP: SMT (0603): 10UF: 20%: 25V: X5R: CERAMIC CHIP")
      (fields
        (field (name "CAP") "1.00E-05")
        (field (name "CASE") "SMT (0603)")
        (field (name "MANUFACTURER") "MURATA")
        (field (name "MATERIAL_TYPE") "CERAMIC CHIP")
        (field (name "MAXINV") "20-0010U-P7")
        (field (name "MFG_PART_NUMBER") "GRM188R61E106MA73")
        (field (name "ORIGINALSYMBOLORIGIN") "(-50,50)")
        (field (name "PACK_TYPE") "0603")
        (field (name "PHYS_PAGE") "2")
        (field (name "REFLOW") "-")
        (field (name "TEMP_RANGE") "-55 DEGC TO +85 DEGC")
        (field (name "TOLERANCE") "20%")
        (field (name "VER") "2")
        (field (name "VLOG_PARAM01") "CAP:INTEGER")
        (field (name "VOLTAGE_RATING") "25V")
      )
      (libsource (lib "eagle-import") (part "EK_CAP_NP"))
    )
    (comp (ref "DS1")
      (value "SFH 7016")
      (footprint "eagle-import:LED_SFH7016")
      (description "DIODE: LED: RED-GREEN-IR: SMT: VF=RED=2.1V: GREEN=2.5V: IR=1.3V: IF=RED=0.04A: GREEN=0.03A: IR=0.06A :NOTE:PURCHASE DIRECT FROM THE MANUFACTURER")
      (fields
        (field (name "MANUFACTURER") "OSRAM")
        (field (name "MAXINV") "ED111000003532")
        (field (name "MFG_PART_NUMBER") "SFH 7016")
        (field (name "ORIGINALSYMBOLORIGIN") "(-125,250)")
        (field (name "PACK_TYPE") "LED_SFH7016")
        (field (name "PHYS_PAGE") "2")
        (field (name "SEC_TYPE") "LED_SFH7016")
        (field (name "TEMP_RANGE") "-40 DEGC TO +85 DEGC")
        (field (name "TOLERANCE") "N/A")
        (field (name "VER") "7")
        (field (name "VOLTAGE_RATING") "RED=2.1V: GREEN=2.5V: IR=1.3V")
      )
      (libsource (lib "eagle-import") (part "LED_6P"))
    )
    (comp (ref "J2")
      (value "5016162575")
      (footprint "eagle-import:MOLEX_501616-2575")
      (description "CONNECTOR: FEMALE: SMT: EASY-ON TYPE FPC CONNECTOR: RIGHT ANGLE: 25PINS :NOTE:DISCONTINUED BY MANUFACTURER")
      (fields
        (field (name "MANUFACTURER") "MOLEX")
        (field (name "MAXINV") "01-501616257525P-29")
        (field (name "MFG_PART_NUMBER") "5016162575")
        (field (name "ORIGINALSYMBOLORIGIN") "(-150,550)")
        (field (name "PACK_TYPE") "RA")
        (field (name "PHYS_PAGE") "2")
        (field (name "REFLOW") "-")
        (field (name "SEC_TYPE") "RA")
        (field (name "TEMP_RANGE") "-40 DEGC TO +85 DEGC")
        (field (name "TOLERANCE") "N/A")
        (field (name "VER") "1")
        (field (name "VOLTAGE_RATING") "+50V")
      )
      (libsource (lib "eagle-import") (part "501616-2575"))
    )
    (comp (ref "R1")
      (value "OPEN")
      (footprint "eagle-import:0402")
      (description "PACKAGE OUTLINE 0402 RESISTOR - EVKIT")
      (fields
        (field (name "CASE") "SMT (0402)")
        (field (name "MANUFACTURER") "N/A")
        (field (name "MATERIAL_TYPE") "N/A")
        (field (name "MAXINV") "N/A")
        (field (name "MFG_PART_NUMBER") "N/A")
        (field (name "ORIGINALSYMBOLORIGIN") "(-75,50)")
        (field (name "PACK_TYPE") "0402RES")
        (field (name "PHYS_PAGE") "2")
        (field (name "POWER_RATING") "N/A")
        (field (name "TEMP_RANGE") "N/A")
        (field (name "TOLERANCE") "N/A")
        (field (name "VER") "2")
        (field (name "VOLTAGE_RATING") "N/A")
      )
      (libsource (lib "eagle-import") (part "EVK_GENERIC_RESISTORSEVK_GENERIC_RESISTORS_1"))
    )
    (comp (ref "R1A")
      (value "OPEN")
      (footprint "eagle-import:RESC0603X33M")
      (description "PACKAGE OUTLINE 0201 RESISTOR - EVKIT")
      (fields
        (field (name "CASE") "SMT (0201)")
        (field (name "MANUFACTURER") "N/A")
        (field (name "MAXINV") "N/A")
        (field (name "MFG_PART_NUMBER") "N/A")
        (field (name "ORIGINALSYMBOLORIGIN") "(-50,75)")
        (field (name "PACK_TYPE") "0201RES")
        (field (name "PHYS_PAGE") "2")
        (field (name "POWER_RATING") "N/A")
        (field (name "TEMP_RANGE") "N/A")
        (field (name "TOLERANCE") "N/A")
        (field (name "VER") "4")
        (field (name "VOLTAGE_RATING") "N/A")
      )
      (libsource (lib "eagle-import") (part "EVK_GENERIC_RESISTORS#1"))
    )
    (comp (ref "R1B")
      (value "0")
      (footprint "eagle-import:RESC0603X33M")
      (description "RES: SMT (0201): 0: 1%: JUMPER: 0.0500W")
      (fields
        (field (name "CASE") "SMT (0201)")
        (field (name "MANUFACTURER") "VISHAY DALE:PANASONIC")
        (field (name "MAXINV") "80-0000R-95")
        (field (name "MFG_PART_NUMBER") "CRCW02010000ZS:ERJ-1GN0R00")
        (field (name "ORIGINALSYMBOLORIGIN") "(-75,50)")
        (field (name "PACK_TYPE") "0201RES")
        (field (name "PHYS_PAGE") "2")
        (field (name "POWER_RATING") "0.05W")
        (field (name "REFLOW") "-")
        (field (name "RES") "0.00000001E00")
        (field (name "TEMP_RANGE") "-55 DEGC TO +155 DEGC")
        (field (name "TOLERANCE") "1%")
        (field (name "VER") "2")
        (field (name "VLOG_PARAM01") "RES:INTEGER")
      )
      (libsource (lib "eagle-import") (part "RES_SMD#1RES_SMD#1"))
    )
    (comp (ref "R2")
      (value "OPEN")
      (footprint "eagle-import:0402")
      (description "PACKAGE OUTLINE 0402 RESISTOR - EVKIT")
      (fields
        (field (name "CASE") "SMT (0402)")
        (field (name "MANUFACTURER") "N/A")
        (field (name "MATERIAL_TYPE") "N/A")
        (field (name "MAXINV") "N/A")
        (field (name "MFG_PART_NUMBER") "N/A")
        (field (name "ORIGINALSYMBOLORIGIN") "(-75,50)")
        (field (name "PACK_TYPE") "0402RES")
        (field (name "PHYS_PAGE") "2")
        (field (name "POWER_RATING") "N/A")
        (field (name "TEMP_RANGE") "N/A")
        (field (name "TOLERANCE") "N/A")
        (field (name "VER") "2")
        (field (name "VOLTAGE_RATING") "N/A")
      )
      (libsource (lib "eagle-import") (part "EVK_GENERIC_RESISTORSEVK_GENERIC_RESISTORS_1"))
    )
    (comp (ref "R3A")
      (value "0")
      (footprint "eagle-import:0402")
      (description "RES: SMT (0402): 0: JUMPER: JUMPER: 0.1000W")
      (fields
        (field (name "CASE") "SMT (0402)")
        (field (name "MANUFACTURER") "PANASONIC")
        (field (name "MATERIAL_TYPE") "THICK FILM")
        (field (name "MAXINV") "80-0000R-26A")
        (field (name "MFG_PART_NUMBER") "ERJ-2GE0R00")
        (field (name "ORIGINALSYMBOLORIGIN") "(-75,50)")
        (field (name "PACK_TYPE") "0402RES")
        (field (name "PHYS_PAGE") "2")
        (field (name "POWER_RATING") "0.10W")
        (field (name "REFLOW") "-")
        (field (name "RES") "0.00000001E00")
        (field (name "TEMP_RANGE") "-55 DEGC TO +155 DEGC")
        (field (name "TOLERANCE") "0%")
        (field (name "VER") "2")
        (field (name "VLOG_PARAM01") "RES:INTEGER")
      )
      (libsource (lib "eagle-import") (part "RES_SMD#1RES_SMD#1_1"))
    )
    (comp (ref "R3B")
      (value "0")
      (footprint "eagle-import:0402")
      (description "RES: SMT (0402): 0: JUMPER: JUMPER: 0.1000W")
      (fields
        (field (name "CASE") "SMT (0402)")
        (field (name "MANUFACTURER") "PANASONIC")
        (field (name "MATERIAL_TYPE") "THICK FILM")
        (field (name "MAXINV") "80-0000R-26A")
        (field (name "MFG_PART_NUMBER") "ERJ-2GE0R00")
        (field (name "ORIGINALSYMBOLORIGIN") "(-75,50)")
        (field (name "PACK_TYPE") "0402RES")
        (field (name "PHYS_PAGE") "2")
        (field (name "POWER_RATING") "0.10W")
        (field (name "REFLOW") "-")
        (field (name "RES") "0.00000001E00")
        (field (name "TEMP_RANGE") "-55 DEGC TO +155 DEGC")
        (field (name "TOLERANCE") "0%")
        (field (name "VARIANT") "DNI")
        (field (name "VER") "2")
        (field (name "VLOG_PARAM01") "RES:INTEGER")
      )
      (libsource (lib "eagle-import") (part "RES_SMD#1RES_SMD#1_1"))
    )
    (comp (ref "R4")
      (value "OPEN")
      (footprint "eagle-import:0402")
      (description "PACKAGE OUTLINE 0402 RESISTOR - EVKIT")
      (fields
        (field (name "CASE") "SMT (0402)")
        (field (name "MANUFACTURER") "N/A")
        (field (name "MATERIAL_TYPE") "N/A")
        (field (name "MAXINV") "N/A")
        (field (name "MFG_PART_NUMBER") "N/A")
        (field (name "ORIGINALSYMBOLORIGIN") "(-75,50)")
        (field (name "PACK_TYPE") "0402RES")
        (field (name "PHYS_PAGE") "2")
        (field (name "POWER_RATING") "N/A")
        (field (name "TEMP_RANGE") "N/A")
        (field (name "TOLERANCE") "N/A")
        (field (name "VER") "2")
        (field (name "VOLTAGE_RATING") "N/A")
      )
      (libsource (lib "eagle-import") (part "EVK_GENERIC_RESISTORSEVK_GENERIC_RESISTORS_1"))
    )
    (comp (ref "R4A")
      (value "0")
      (footprint "eagle-import:0402")
      (description "RES: SMT (0402): 0: JUMPER: JUMPER: 0.1000W")
      (fields
        (field (name "CASE") "SMT (0402)")
        (field (name "MANUFACTURER") "PANASONIC")
        (field (name "MATERIAL_TYPE") "THICK FILM")
        (field (name "MAXINV") "80-0000R-26A")
        (field (name "MFG_PART_NUMBER") "ERJ-2GE0R00")
        (field (name "ORIGINALSYMBOLORIGIN") "(-75,50)")
        (field (name "PACK_TYPE") "0402RES")
        (field (name "PHYS_PAGE") "2")
        (field (name "POWER_RATING") "0.10W")
        (field (name "REFLOW") "-")
        (field (name "RES") "0.00000001E00")
        (field (name "TEMP_RANGE") "-55 DEGC TO +155 DEGC")
        (field (name "TOLERANCE") "0%")
        (field (name "VER") "2")
        (field (name "VLOG_PARAM01") "RES:INTEGER")
      )
      (libsource (lib "eagle-import") (part "RES_SMD#1RES_SMD#1_1"))
    )
    (comp (ref "R4B")
      (value "0")
      (footprint "eagle-import:0402")
      (description "RES: SMT (0402): 0: JUMPER: JUMPER: 0.1000W")
      (fields
        (field (name "CASE") "SMT (0402)")
        (field (name "MANUFACTURER") "PANASONIC")
        (field (name "MATERIAL_TYPE") "THICK FILM")
        (field (name "MAXINV") "80-0000R-26A")
        (field (name "MFG_PART_NUMBER") "ERJ-2GE0R00")
        (field (name "ORIGINALSYMBOLORIGIN") "(-75,50)")
        (field (name "PACK_TYPE") "0402RES")
        (field (name "PHYS_PAGE") "2")
        (field (name "POWER_RATING") "0.10W")
        (field (name "REFLOW") "-")
        (field (name "RES") "0.00000001E00")
        (field (name "TEMP_RANGE") "-55 DEGC TO +155 DEGC")
        (field (name "TOLERANCE") "0%")
        (field (name "VARIANT") "DNI")
        (field (name "VER") "2")
        (field (name "VLOG_PARAM01") "RES:INTEGER")
      )
      (libsource (lib "eagle-import") (part "RES_SMD#1RES_SMD#1_1"))
    )
    (comp (ref "R5")
      (value "0")
      (footprint "eagle-import:RESC0603X33M")
      (description "RES: SMT (0201): 0: 1%: JUMPER: 0.0500W")
      (fields
        (field (name "CASE") "SMT (0201)")
        (field (name "MANUFACTURER") "VISHAY DALE:PANASONIC")
        (field (name "MATERIAL_TYPE") "THICK FILM")
        (field (name "MAXINV") "80-0000R-95")
        (field (name "MFG_PART_NUMBER") "CRCW02010000ZS:ERJ-1GN0R00")
        (field (name "ORIGINALSYMBOLORIGIN") "(-75,50)")
        (field (name "PACK_TYPE") "0201RES")
        (field (name "PHYS_PAGE") "2")
        (field (name "POWER_RATING") "0.05W")
        (field (name "REFLOW") "-")
        (field (name "RES") "0.00000001E00")
        (field (name "TEMP_RANGE") "-55 DEGC TO +155 DEGC")
        (field (name "TOLERANCE") "1%")
        (field (name "VER") "2")
        (field (name "VLOG_PARAM01") "RES:INTEGER")
      )
      (libsource (lib "eagle-import") (part "RES_SMD#1RES_SMD#1"))
    )
    (comp (ref "R6")
      (value "0")
      (footprint "eagle-import:RESC0603X33M")
      (description "RES: SMT (0201): 0: 1%: JUMPER: 0.0500W")
      (fields
        (field (name "CASE") "SMT (0201)")
        (field (name "MANUFACTURER") "VISHAY DALE:PANASONIC")
        (field (name "MATERIAL_TYPE") "THICK FILM")
        (field (name "MAXINV") "80-0000R-95")
        (field (name "MFG_PART_NUMBER") "CRCW02010000ZS:ERJ-1GN0R00")
        (field (name "ORIGINALSYMBOLORIGIN") "(-75,50)")
        (field (name "PACK_TYPE") "0201RES")
        (field (name "PHYS_PAGE") "2")
        (field (name "POWER_RATING") "0.05W")
        (field (name "REFLOW") "-")
        (field (name "RES") "0.00000001E00")
        (field (name "TEMP_RANGE") "-55 DEGC TO +155 DEGC")
        (field (name "TOLERANCE") "1%")
        (field (name "VER") "2")
        (field (name "VLOG_PARAM01") "RES:INTEGER")
      )
      (libsource (lib "eagle-import") (part "RES_SMD#1RES_SMD#1"))
    )
    (comp (ref "R7")
      (value "0")
      (footprint "eagle-import:RESC0603X33M")
      (description "RES: SMT (0201): 0: 1%: JUMPER: 0.0500W")
      (fields
        (field (name "CASE") "SMT (0201)")
        (field (name "MANUFACTURER") "VISHAY DALE:PANASONIC")
        (field (name "MATERIAL_TYPE") "THICK FILM")
        (field (name "MAXINV") "80-0000R-95")
        (field (name "MFG_PART_NUMBER") "CRCW02010000ZS:ERJ-1GN0R00")
        (field (name "ORIGINALSYMBOLORIGIN") "(-75,50)")
        (field (name "PACK_TYPE") "0201RES")
        (field (name "PHYS_PAGE") "2")
        (field (name "POWER_RATING") "0.05W")
        (field (name "REFLOW") "-")
        (field (name "RES") "0.00000001E00")
        (field (name "TEMP_RANGE") "-55 DEGC TO +155 DEGC")
        (field (name "TOLERANCE") "1%")
        (field (name "VARIANT") "DNI")
        (field (name "VER") "2")
        (field (name "VLOG_PARAM01") "RES:INTEGER")
      )
      (libsource (lib "eagle-import") (part "RES_SMD#1RES_SMD#1"))
    )
    (comp (ref "R12")
      (value "0")
      (footprint "eagle-import:RESC0603X33M")
      (description "RES: SMT (0201): 0: 1%: JUMPER: 0.0500W")
      (fields
        (field (name "CASE") "SMT (0201)")
        (field (name "MANUFACTURER") "VISHAY DALE:PANASONIC")
        (field (name "MATERIAL_TYPE") "THICK FILM")
        (field (name "MAXINV") "80-0000R-95")
        (field (name "MFG_PART_NUMBER") "CRCW02010000ZS:ERJ-1GN0R00")
        (field (name "ORIGINALSYMBOLORIGIN") "(-75,50)")
        (field (name "PACK_TYPE") "0201RES")
        (field (name "PHYS_PAGE") "2")
        (field (name "POWER_RATING") "0.05W")
        (field (name "REFLOW") "-")
        (field (name "RES") "0.00000001E00")
        (field (name "TEMP_RANGE") "-55 DEGC TO +155 DEGC")
        (field (name "TOLERANCE") "1%")
        (field (name "VER") "2")
        (field (name "VLOG_PARAM01") "RES:INTEGER")
      )
      (libsource (lib "eagle-import") (part "RES_SMD#1RES_SMD#1"))
    )
    (comp (ref "R14")
      (value "0")
      (footprint "eagle-import:RESC0603X33M")
      (description "RES: SMT (0201): 0: 1%: JUMPER: 0.0500W")
      (fields
        (field (name "CASE") "SMT (0201)")
        (field (name "MANUFACTURER") "VISHAY DALE:PANASONIC")
        (field (name "MAXINV") "80-0000R-95")
        (field (name "MFG_PART_NUMBER") "CRCW02010000ZS:ERJ-1GN0R00")
        (field (name "ORIGINALSYMBOLORIGIN") "(-75,50)")
        (field (name "PACK_TYPE") "0201RES")
        (field (name "PHYS_PAGE") "2")
        (field (name "POWER_RATING") "0.05W")
        (field (name "REFLOW") "-")
        (field (name "RES") "0.00000001E00")
        (field (name "TEMP_RANGE") "-55 DEGC TO +155 DEGC")
        (field (name "TOLERANCE") "1%")
        (field (name "VER") "2")
        (field (name "VLOG_PARAM01") "RES:INTEGER")
      )
      (libsource (lib "eagle-import") (part "RES_SMD#1RES_SMD#1"))
    )
    (comp (ref "R37")
      (value "SHORT")
      (footprint "eagle-import:RESC0603X23L_SHORT")
      (description "PACKAGE OUTLINE 0201 RESISTOR - EVKIT FORM FACTOR FOOTRINT")
      (fields
        (field (name "CASE") "SMT (0201)")
        (field (name "MANUFACTURER") "N/A")
        (field (name "MATERIAL_TYPE") "N/A")
        (field (name "MAXINV") "N/A")
        (field (name "MFG_PART_NUMBER") "N/A")
        (field (name "ORIGINALSYMBOLORIGIN") "(-75,50)")
        (field (name "PACK_TYPE") "0201RES_FF")
        (field (name "PHYS_PAGE") "2")
        (field (name "POWER_RATING") "N/A")
        (field (name "TEMP_RANGE") "N/A")
        (field (name "TOLERANCE") "N/A")
        (field (name "VER") "2")
        (field (name "VOLTAGE_RATING") "N/A")
      )
      (libsource (lib "eagle-import") (part "EVK_GENERIC_RESISTORSEVK_GENERIC_RESISTORS"))
    )
    (comp (ref "R38")
      (value "SHORT")
      (footprint "eagle-import:RESC0603X23L_SHORT")
      (description "PACKAGE OUTLINE 0201 RESISTOR - EVKIT FORM FACTOR FOOTRINT")
      (fields
        (field (name "CASE") "SMT (0201)")
        (field (name "MANUFACTURER") "N/A")
        (field (name "MATERIAL_TYPE") "N/A")
        (field (name "MAXINV") "N/A")
        (field (name "MFG_PART_NUMBER") "N/A")
        (field (name "ORIGINALSYMBOLORIGIN") "(-75,50)")
        (field (name "PACK_TYPE") "0201RES_FF")
        (field (name "PHYS_PAGE") "2")
        (field (name "POWER_RATING") "N/A")
        (field (name "TEMP_RANGE") "N/A")
        (field (name "TOLERANCE") "N/A")
        (field (name "VER") "2")
        (field (name "VOLTAGE_RATING") "N/A")
      )
      (libsource (lib "eagle-import") (part "EVK_GENERIC_RESISTORSEVK_GENERIC_RESISTORS"))
    )
    (comp (ref "U2")
      (value "VEMD8080")
      (footprint "eagle-import:DIO_VEMD8080")
      (description "DIODE: PIN: SMT: VRM=20V: IF=0.05A :NOTE:PURCHASE DIRECT FROM THE MANUFACTURER")
      (fields
        (field (name "MANUFACTURER") "VISHAY")
        (field (name "MAXINV") "ED1259")
        (field (name "MFG_PART_NUMBER") "VEMD8080")
        (field (name "ORIGINALSYMBOLORIGIN") "(-150,200)")
        (field (name "PACK_TYPE") "SMD")
        (field (name "PHYS_PAGE") "2")
        (field (name "SEC_TYPE") "SMD")
        (field (name "TEMP_RANGE") "-40 DEGC TO +85 DEGC")
        (field (name "TOLERANCE") "N/A")
        (field (name "VER") "1")
        (field (name "VOLTAGE_RATING") "20V")
      )
      (libsource (lib "eagle-import") (part "DIO_PIN_8P"))
    )
    (comp (ref "U3")
      (value "VEMD8080")
      (footprint "eagle-import:DIO_VEMD8080")
      (description "DIODE: PIN: SMT: VRM=20V: IF=0.05A :NOTE:PURCHASE DIRECT FROM THE MANUFACTURER")
      (fields
        (field (name "MANUFACTURER") "VISHAY")
        (field (name "MAXINV") "ED1259")
        (field (name "MFG_PART_NUMBER") "VEMD8080")
        (field (name "ORIGINALSYMBOLORIGIN") "(-150,200)")
        (field (name "PACK_TYPE") "SMD")
        (field (name "PHYS_PAGE") "2")
        (field (name "SEC_TYPE") "SMD")
        (field (name "TEMP_RANGE") "-40 DEGC TO +85 DEGC")
        (field (name "TOLERANCE") "N/A")
        (field (name "VER") "1")
        (field (name "VOLTAGE_RATING") "20V")
      )
      (libsource (lib "eagle-import") (part "DIO_PIN_8P"))
    )
    (comp (ref "U4")
      (value "LIS2DS12")
      (footprint "eagle-import:STMC_LGA-12")
      (description "IC: MEMS: DIGITAL OUTPUT MOTION SENSOR: ULTRA-LOW-POWER HIGH-PERFORMANCE 3-AXIS PICO ACCELEROMETER: MICROELECTROMECHANICAL SYSTEMS: LGA12: NOTE: MANUFACTURER")
      (fields
        (field (name "CASE") "LGA12")
        (field (name "MANUFACTURER") "ST MICROELECTRONICS")
        (field (name "MAXINV") "EQ111000005315")
        (field (name "MFG_PART_NUMBER") "LIS2DS12")
        (field (name "ORIGINALSYMBOLORIGIN") "(-375,375)")
        (field (name "PACK_TYPE") "LGA12")
        (field (name "PHYS_PAGE") "2")
        (field (name "TEMP_RANGE") "-40 DEGC TO +85 DEGC")
        (field (name "TOLERANCE") "N/A")
        (field (name "VER") "1")
        (field (name "VOLTAGE_RATING") "+1.62V TO +1.98V")
      )
      (libsource (lib "eagle-import") (part "LIS2DS12"))
    )
    (comp (ref "U14")
      (value "VEMD8080")
      (footprint "eagle-import:DIO_VEMD8080")
      (description "DIODE: PIN: SMT: VRM=20V: IF=0.05A :NOTE:PURCHASE DIRECT FROM THE MANUFACTURER")
      (fields
        (field (name "MANUFACTURER") "VISHAY")
        (field (name "MAXINV") "ED1259")
        (field (name "MFG_PART_NUMBER") "VEMD8080")
        (field (name "ORIGINALSYMBOLORIGIN") "(-150,200)")
        (field (name "PACK_TYPE") "SMD")
        (field (name "PHYS_PAGE") "2")
        (field (name "SEC_TYPE") "SMD")
        (field (name "TEMP_RANGE") "-40 DEGC TO +85 DEGC")
        (field (name "TOLERANCE") "N/A")
        (field (name "VER") "1")
        (field (name "VOLTAGE_RATING") "20V")
      )
      (libsource (lib "eagle-import") (part "DIO_PIN_8P"))
    )
    (comp (ref "U20")
      (value "SIT1572AI-J3-18E-DCC-32.768")
      (footprint "eagle-import:OSC_SIT1572XX-JX-XXX")
      (description "OSCILLATOR: CSP 1.5 MM X 0.8 MM: 15PF: 32.768KHZ : +/-10PPM")
      (fields
        (field (name "MANUFACTURER") "SITIME CORPORATION")
        (field (name "MAXINV") "EX111000005339")
        (field (name "MFG_PART_NUMBER") "SIT1572AI-J3-18E-DCC-32.768")
        (field (name "ORIGINALSYMBOLORIGIN") "(-175,200)")
        (field (name "PACK_TYPE") "SMD")
        (field (name "PHYS_PAGE") "2")
        (field (name "TEMP_RANGE") "-40 DEGC TO +85 DEGC")
        (field (name "TOLERANCE") "N/A")
        (field (name "VER") "1")
        (field (name "VOLTAGE_RATING") "+1.8V")
      )
      (libsource (lib "eagle-import") (part "SIT1572"))
    )
  )
  (nets
    (net (code "1") (name "+1.8V") (class "Default")
      (node (ref "C1") (pin "2") (pinfunction "2_2") (pintype "bidirectional"))
      (node (ref "C22") (pin "2") (pinfunction "2_2") (pintype "bidirectional"))
      (node (ref "C24") (pin "2") (pinfunction "2_2") (pintype "bidirectional"))
      (node (ref "C3") (pin "2") (pinfunction "2_2") (pintype "bidirectional"))
      (node (ref "C38") (pin "2") (pinfunction "2_2") (pintype "bidirectional"))
      (node (ref "C4") (pin "2") (pinfunction "2_2") (pintype "bidirectional"))
      (node (ref "C8") (pin "2") (pinfunction "2_2") (pintype "bidirectional"))
      (node (ref "J2") (pin "15") (pinfunction "15_15") (pintype "bidirectional"))
      (node (ref "J2") (pin "20") (pinfunction "20_20") (pintype "bidirectional"))
      (node (ref "R11") (pin "2") (pinfunction "2_2") (pintype "bidirectional"))
      (node (ref "R16") (pin "2") (pinfunction "2_2") (pintype "bidirectional"))
      (node (ref "R17") (pin "2") (pinfunction "2_2") (pintype "bidirectional"))
      (node (ref "R28") (pin "1") (pinfunction "1_1") (pintype "bidirectional"))
      (node (ref "R29") (pin "1") (pinfunction "1_1") (pintype "bidirectional"))
      (node (ref "U1") (pin "D6") (pinfunction "AVDD_D6") (pintype "bidirectional"))
      (node (ref "U1") (pin "E6") (pinfunction "DVDD_E6") (pintype "bidirectional"))
      (node (ref "U20") (pin "3") (pinfunction "VDD_3") (pintype "input"))
      (node (ref "U4") (pin "10") (pinfunction "VDDIO_10") (pintype "input"))
      (node (ref "U4") (pin "9") (pinfunction "VDD_9") (pintype "input"))
    )
    (net (code "2") (name "ACC_CS") (class "Default")
      (node (ref "J2") (pin "11") (pinfunction "11_11") (pintype "bidirectional"))
      (node (ref "U4") (pin "2") (pinfunction "CS_2") (pintype "bidirectional"))
    )
    (net (code "3") (name "ACC_INT1") (class "Default")
      (node (ref "R1") (pin "1") (pinfunction "1_1") (pintype "bidirectional"))
      (node (ref "R5") (pin "1") (pinfunction "1_1") (pintype "bidirectional"))
    )
    (net (code "4") (name "ACC_INT2") (class "Default")
      (node (ref "R12") (pin "1") (pinfunction "1_1") (pintype "bidirectional"))
      (node (ref "R4") (pin "1") (pinfunction "1_1") (pintype "bidirectional"))
      (node (ref "U4") (pin "11") (pinfunction "INT2_11") (pintype "input"))
    )
    (net (code "5") (name "AFE_INT1") (class "Default")
      (node (ref "R16") (pin "1") (pinfunction "1_1") (pintype "bidirectional"))
      (node (ref "R2") (pin "1") (pinfunction "1_1") (pintype "bidirectional"))
      (node (ref "U1") (pin "C4") (pinfunction "INT1_C4") (pintype "bidirectional"))
    )
    (net (code "6") (name "AFE_INT2") (class "Default")
      (node (ref "R14") (pin "1") (pinfunction "1_1") (pintype "bidirectional"))
      (node (ref "R17") (pin "1") (pinfunction "1_1") (pintype "bidirectional"))
      (node (ref "U1") (pin "C5") (pinfunction "INT2_C5") (pintype "bidirectional"))
    )
    (net (code "7") (name "AGND") (class "Default")
      (node (ref "C12") (pin "1") (pinfunction "1_1") (pintype "bidirectional"))
      (node (ref "C22") (pin "1") (pinfunction "1_1") (pintype "bidirectional"))
      (node (ref "C24") (pin "1") (pinfunction "1_1") (pintype "bidirectional"))
      (node (ref "C38") (pin "1") (pinfunction "1_1") (pintype "bidirectional"))
      (node (ref "C44") (pin "1") (pinfunction "1_1") (pintype "bidirectional"))
      (node (ref "C45") (pin "2") (pinfunction "2_2") (pintype "bidirectional"))
      (node (ref "C5") (pin "1") (pinfunction "1_1") (pintype "bidirectional"))
      (node (ref "C6") (pin "1") (pinfunction "1_1") (pintype "bidirectional"))
      (node (ref "R18") (pin "1") (pinfunction "1_1") (pintype "bidirectional"))
      (node (ref "R37") (pin "1") (pinfunction "1_1") (pintype "bidirectional"))
      (node (ref "R38") (pin "2") (pinfunction "2_2") (pintype "bidirectional"))
      (node (ref "U1") (pin "C3") (pinfunction "AGND_C3") (pintype "bidirectional"))
      (node (ref "U1") (pin "C6") (pinfunction "AGND_C6") (pintype "bidirectional"))
      (node (ref "U1") (pin "F6") (pinfunction "DGND_F6") (pintype "bidirectional"))
      (node (ref "U20") (pin "4") (pinfunction "GND_4") (pintype "input"))
    )
    (net (code "8") (name "CSB") (class "Default")
      (node (ref "J2") (pin "3") (pinfunction "3_3") (pintype "bidirectional"))
      (node (ref "U1") (pin "D5") (pinfunction "CSB_D5") (pintype "bidirectional"))
    )
    (net (code "9") (name "ECGN") (class "Default")
      (node (ref "C18") (pin "2") (pinfunction "2_2") (pintype "bidirectional"))
      (node (ref "C44") (pin "2") (pinfunction "2_2") (pintype "bidirectional"))
      (node (ref "R45") (pin "2") (pinfunction "2_2") (pintype "bidirectional"))
      (node (ref "U1") (pin "A6") (pinfunction "ECGN_A6") (pintype "bidirectional"))
    )
    (net (code "10") (name "ECGP") (class "Default")
      (node (ref "C18") (pin "1") (pinfunction "1_1") (pintype "bidirectional"))
      (node (ref "C45") (pin "1") (pinfunction "1_1") (pintype "bidirectional"))
      (node (ref "R46") (pin "2") (pinfunction "2_2") (pintype "bidirectional"))
      (node (ref "U1") (pin "A5") (pinfunction "ECGP_A5") (pintype "bidirectional"))
    )
    (net (code "11") (name "FCLK") (class "Default")
      (node (ref "R1A") (pin "2") (pinfunction "2_2") (pintype "bidirectional"))
      (node (ref "R1B") (pin "2") (pinfunction "2_2") (pintype "bidirectional"))
      (node (ref "U1") (pin "E5") (pinfunction "FCLK_E5") (pintype "bidirectional"))
    )
    (net (code "12") (name "I2C_SEL") (class "Default")
      (node (ref "R11") (pin "1") (pinfunction "1_1") (pintype "bidirectional"))
      (node (ref "R18") (pin "2") (pinfunction "2_2") (pintype "bidirectional"))
      (node (ref "U1") (pin "D2") (pinfunction "I2C_SEL_D2") (pintype "bidirectional"))
    )
    (net (code "13") (name "LED1_DRV") (class "Default")
      (node (ref "DS1") (pin "3") (pinfunction "G_3") (pintype "bidirectional"))
      (node (ref "U1") (pin "E1") (pinfunction "LED1_DRV_E1") (pintype "bidirectional"))
    )
    (net (code "14") (name "LED2_DRV") (class "Default")
      (node (ref "DS1") (pin "1") (pinfunction "IR_1") (pintype "bidirectional"))
      (node (ref "U1") (pin "F1") (pinfunction "LED2_DRV_F1") (pintype "bidirectional"))
    )
    (net (code "15") (name "LED3_DRV") (class "Default")
      (node (ref "DS1") (pin "4") (pinfunction "R_4") (pintype "bidirectional"))
      (node (ref "U1") (pin "E2") (pinfunction "LED3_DRV_E2") (pintype "bidirectional"))
    )
    (net (code "16") (name "MC_FCLK") (class "Default")
      (node (ref "J2") (pin "18") (pinfunction "18_18") (pintype "bidirectional"))
      (node (ref "R1A") (pin "1") (pinfunction "1_1") (pintype "bidirectional"))
      (node (ref "R3B") (pin "1") (pinfunction "1_1") (pintype "bidirectional"))
    )
    (net (code "17") (name "Net-(J1-Pad1)") (class "Default")
      (node (ref "J1") (pin "1") (pinfunction "1_1") (pintype "bidirectional"))
      (node (ref "J1") (pin "2") (pinfunction "2_2") (pintype "bidirectional"))
      (node (ref "J1") (pin "3") (pinfunction "3_3") (pintype "bidirectional"))
      (node (ref "R46") (pin "1") (pinfunction "1_1") (pintype "bidirectional"))
    )
    (net (code "18") (name "Net-(J2-Pad1)") (class "Default")
      (node (ref "J2") (pin "1") (pinfunction "1_1") (pintype "bidirectional"))
      (node (ref "R2") (pin "2") (pinfunction "2_2") (pintype "bidirectional"))
      (node (ref "R4") (pin "2") (pinfunction "2_2") (pintype "bidirectional"))
      (node (ref "R7") (pin "2") (pinfunction "2_2") (pintype "bidirectional"))
    )
    (net (code "19") (name "Net-(J2-Pad7)") (class "Default")
      (node (ref "J2") (pin "7") (pinfunction "7_7") (pintype "bidirectional"))
      (node (ref "R3A") (pin "2") (pinfunction "2_2") (pintype "bidirectional"))
    )
    (net (code "20") (name "Net-(J2-Pad9)") (class "Default")
      (node (ref "J2") (pin "9") (pinfunction "9_9") (pintype "bidirectional"))
      (node (ref "R4A") (pin "2") (pinfunction "2_2") (pintype "bidirectional"))
    )
    (net (code "21") (name "Net-(J2-Pad13)") (class "Default")
      (node (ref "J2") (pin "13") (pinfunction "13_13") (pintype "bidirectional"))
      (node (ref "R14") (pin "2") (pinfunction "2_2") (pintype "bidirectional"))
    )
    (net (code "22") (name "Net-(J2-Pad17)") (class "Default")
      (node (ref "J2") (pin "17") (pinfunction "17_17") (pintype "bidirectional"))
      (node (ref "R4B") (pin "2") (pinfunction "2_2") (pintype "bidirectional"))
    )
    (net (code "23") (name "Net-(J2-Pad25)") (class "Default")
      (node (ref "J2") (pin "25") (pinfunction "25_25") (pintype "bidirectional"))
      (node (ref "R1") (pin "2") (pinfunction "2_2") (pintype "bidirectional"))
      (node (ref "R12") (pin "2") (pinfunction "2_2") (pintype "bidirectional"))
    )
    (net (code "24") (name "Net-(RLD-TP1)") (class "Default")
      (node (ref "R3") (pin "1") (pinfunction "1_1") (pintype "bidirectional"))
      (node (ref "R56") (pin "1") (pinfunction "1_1") (pintype "bidirectional"))
      (node (ref "RLD") (pin "1") (pinfunction "TP1_1") (pintype "bidirectional"))
      (node (ref "TP3") (pin "1") (pinfunction "TP1_1") (pintype "bidirectional"))
    )
    (net (code "25") (name "Net-(TP2-TP1)") (class "Default")
      (node (ref "R3") (pin "2") (pinfunction "2_2") (pintype "bidirectional"))
      (node (ref "R45") (pin "1") (pinfunction "1_1") (pintype "bidirectional"))
      (node (ref "TP2") (pin "1") (pinfunction "TP1_1") (pintype "bidirectional"))
    )
    (net (code "26") (name "Net-(U1-CAPN)") (class "Default")
      (node (ref "C7") (pin "1") (pinfunction "1_1") (pintype "bidirectional"))
      (node (ref "U1") (pin "B6") (pinfunction "CAPN_B6") (pintype "bidirectional"))
    )
    (net (code "27") (name "Net-(U1-CAPP)") (class "Default")
      (node (ref "C7") (pin "2") (pinfunction "2_2") (pintype "bidirectional"))
      (node (ref "U1") (pin "B5") (pinfunction "CAPP_B5") (pintype "bidirectional"))
    )
    (net (code "28") (name "Net-(U1-RLD_INV)") (class "Default")
      (node (ref "R10") (pin "1") (pinfunction "1_1") (pintype "bidirectional"))
      (node (ref "U1") (pin "A3") (pinfunction "RLD_INV_A3") (pintype "bidirectional"))
    )
    (net (code "29") (name "Net-(U1-VMID_ECG)") (class "Default")
      (node (ref "C5") (pin "2") (pinfunction "2_2") (pintype "bidirectional"))
      (node (ref "U1") (pin "B3") (pinfunction "VMID_ECG_B3") (pintype "bidirectional"))
    )
    (net (code "30") (name "Net-(U1-VREF_ECG)") (class "Default")
      (node (ref "C6") (pin "2") (pinfunction "2_2") (pintype "bidirectional"))
      (node (ref "U1") (pin "B4") (pinfunction "VREF_ECG_B4") (pintype "bidirectional"))
    )
    (net (code "31") (name "Net-(U1-VREF_PPG)") (class "Default")
      (node (ref "C12") (pin "2") (pinfunction "2_2") (pintype "bidirectional"))
      (node (ref "U1") (pin "C2") (pinfunction "VREF_PPG_C2") (pintype "bidirectional"))
    )
    (net (code "32") (name "Net-(U4-INT1)") (class "Default")
      (node (ref "R5") (pin "2") (pinfunction "2_2") (pintype "bidirectional"))
      (node (ref "R6") (pin "2") (pinfunction "2_2") (pintype "bidirectional"))
      (node (ref "U4") (pin "12") (pinfunction "INT1_12") (pintype "input"))
    )
    (net (code "33") (name "Net-(U20-CLK_OUT)") (class "Default")
      (node (ref "R1B") (pin "1") (pinfunction "1_1") (pintype "bidirectional"))
      (node (ref "U20") (pin "2") (pinfunction "CLK_OUT_2") (pintype "output"))
    )
    (net (code "34") (name "PD1_IN") (class "Default")
      (node (ref "U1") (pin "A1") (pinfunction "PD1_IN_A1") (pintype "bidirectional"))
      (node (ref "U3") (pin "1") (pinfunction "K_1") (pintype "bidirectional"))
      (node (ref "U3") (pin "2") (pinfunction "K_2") (pintype "bidirectional"))
      (node (ref "U3") (pin "3") (pinfunction "K_3") (pintype "bidirectional"))
      (node (ref "U3") (pin "4") (pinfunction "K_4") (pintype "bidirectional"))
      (node (ref "U3") (pin "6") (pinfunction "K_6") (pintype "bidirectional"))
      (node (ref "U3") (pin "7") (pinfunction "K_7") (pintype "bidirectional"))
      (node (ref "U3") (pin "8") (pinfunction "K_8") (pintype "bidirectional"))
    )
    (net (code "35") (name "PD2_IN") (class "Default")
      (node (ref "U1") (pin "A2") (pinfunction "PD2_IN_A2") (pintype "bidirectional"))
      (node (ref "U2") (pin "1") (pinfunction "K_1") (pintype "bidirectional"))
      (node (ref "U2") (pin "2") (pinfunction "K_2") (pintype "bidirectional"))
      (node (ref "U2") (pin "3") (pinfunction "K_3") (pintype "bidirectional"))
      (node (ref "U2") (pin "4") (pinfunction "K_4") (pintype "bidirectional"))
      (node (ref "U2") (pin "6") (pinfunction "K_6") (pintype "bidirectional"))
      (node (ref "U2") (pin "7") (pinfunction "K_7") (pintype "bidirectional"))
      (node (ref "U2") (pin "8") (pinfunction "K_8") (pintype "bidirectional"))
    )
    (net (code "36") (name "PD3_IN") (class "Default")
      (node (ref "U1") (pin "B1") (pinfunction "PD3_IN_B1") (pintype "bidirectional"))
      (node (ref "U14") (pin "1") (pinfunction "K_1") (pintype "bidirectional"))
      (node (ref "U14") (pin "2") (pinfunction "K_2") (pintype "bidirectional"))
      (node (ref "U14") (pin "3") (pinfunction "K_3") (pintype "bidirectional"))
      (node (ref "U14") (pin "4") (pinfunction "K_4") (pintype "bidirectional"))
      (node (ref "U14") (pin "6") (pinfunction "K_6") (pintype "bidirectional"))
      (node (ref "U14") (pin "7") (pinfunction "K_7") (pintype "bidirectional"))
      (node (ref "U14") (pin "8") (pinfunction "K_8") (pintype "bidirectional"))
    )
    (net (code "37") (name "PD_GND") (class "Default")
      (node (ref "R37") (pin "2") (pinfunction "2_2") (pintype "bidirectional"))
      (node (ref "U1") (pin "C1") (pinfunction "PD_GND_C1") (pintype "bidirectional"))
      (node (ref "U14") (pin "5") (pinfunction "A_5") (pintype "bidirectional"))
      (node (ref "U2") (pin "5") (pinfunction "A_5") (pintype "bidirectional"))
      (node (ref "U3") (pin "5") (pinfunction "A_5") (pintype "bidirectional"))
    )
    (net (code "38") (name "PGND") (class "Default")
      (node (ref "C1") (pin "1") (pinfunction "1_1") (pintype "bidirectional"))
      (node (ref "C2") (pin "1") (pinfunction "1_1") (pintype "bidirectional"))
      (node (ref "C3") (pin "1") (pinfunction "1_1") (pintype "bidirectional"))
      (node (ref "C30") (pin "1") (pinfunction "1_1") (pintype "bidirectional"))
      (node (ref "C35") (pin "1") (pinfunction "1_1") (pintype "bidirectional"))
      (node (ref "C4") (pin "1") (pinfunction "1_1") (pintype "bidirectional"))
      (node (ref "C8") (pin "1") (pinfunction "1_1") (pintype "bidirectional"))
      (node (ref "C9") (pin "1") (pinfunction "1_1") (pintype "bidirectional"))
      (node (ref "J2") (pin "10") (pinfunction "10_10") (pintype "bidirectional"))
      (node (ref "J2") (pin "12") (pinfunction "12_12") (pintype "bidirectional"))
      (node (ref "J2") (pin "14") (pinfunction "14_14") (pintype "bidirectional"))
      (node (ref "J2") (pin "16") (pinfunction "16_16") (pintype "bidirectional"))
      (node (ref "J2") (pin "19") (pinfunction "19_19") (pintype "bidirectional"))
      (node (ref "J2") (pin "2") (pinfunction "2_2") (pintype "bidirectional"))
      (node (ref "J2") (pin "21") (pinfunction "21_21") (pintype "bidirectional"))
      (node (ref "J2") (pin "24") (pinfunction "24_24") (pintype "bidirectional"))
      (node (ref "J2") (pin "26") (pinfunction "26_26") (pintype "bidirectional"))
      (node (ref "J2") (pin "27") (pinfunction "27_27") (pintype "bidirectional"))
      (node (ref "J2") (pin "4") (pinfunction "4_4") (pintype "bidirectional"))
      (node (ref "J2") (pin "6") (pinfunction "6_6") (pintype "bidirectional"))
      (node (ref "J2") (pin "8") (pinfunction "8_8") (pintype "bidirectional"))
      (node (ref "R38") (pin "1") (pinfunction "1_1") (pintype "bidirectional"))
      (node (ref "U1") (pin "F4") (pinfunction "PGND_F4") (pintype "bidirectional"))
      (node (ref "U4") (pin "5") (pinfunction "NC_5") (pintype "bidirectional"))
      (node (ref "U4") (pin "6") (pinfunction "GND_6") (pintype "input"))
      (node (ref "U4") (pin "7") (pinfunction "RES_7") (pintype "input"))
      (node (ref "U4") (pin "8") (pinfunction "GND_8") (pintype "input"))
    )
    (net (code "39") (name "RLD") (class "Default")
      (node (ref "R10") (pin "2") (pinfunction "2_2") (pintype "bidirectional"))
      (node (ref "R56") (pin "2") (pinfunction "2_2") (pintype "bidirectional"))
      (node (ref "U1") (pin "A4") (pinfunction "RLD_A4") (pintype "bidirectional"))
    )
    (net (code "40") (name "SCLK{slash}SCL") (class "Default")
      (node (ref "R28") (pin "2") (pinfunction "2_2") (pintype "bidirectional"))
      (node (ref "R3A") (pin "1") (pinfunction "1_1") (pintype "bidirectional"))
      (node (ref "R3B") (pin "2") (pinfunction "2_2") (pintype "bidirectional"))
      (node (ref "U1") (pin "E4") (pinfunction "SCLK/SCL_E4") (pintype "bidirectional"))
      (node (ref "U4") (pin "1") (pinfunction "SCL/SPC_1") (pintype "bidirectional"))
    )
    (net (code "41") (name "SDI{slash}SDA") (class "Default")
      (node (ref "R29") (pin "2") (pinfunction "2_2") (pintype "bidirectional"))
      (node (ref "R4A") (pin "1") (pinfunction "1_1") (pintype "bidirectional"))
      (node (ref "R4B") (pin "1") (pinfunction "1_1") (pintype "bidirectional"))
      (node (ref "U1") (pin "D4") (pinfunction "SDI/SDA_D4") (pintype "bidirectional"))
      (node (ref "U4") (pin "4") (pinfunction "SDA/SDI/SDO_4") (pintype "bidirectional"))
    )
    (net (code "42") (name "SDO") (class "Default")
      (node (ref "J2") (pin "5") (pinfunction "5_5") (pintype "bidirectional"))
      (node (ref "U1") (pin "D3") (pinfunction "SDO_D3") (pintype "bidirectional"))
      (node (ref "U4") (pin "3") (pinfunction "SDO/SA0_3") (pintype "bidirectional"))
    )
    (net (code "43") (name "TRIG") (class "Default")
      (node (ref "R6") (pin "1") (pinfunction "1_1") (pintype "bidirectional"))
      (node (ref "R7") (pin "1") (pinfunction "1_1") (pintype "bidirectional"))
      (node (ref "U1") (pin "F5") (pinfunction "TRIG_F5") (pintype "bidirectional"))
    )
    (net (code "44") (name "VLED") (class "Default")
      (node (ref "C2") (pin "2") (pinfunction "2_2") (pintype "bidirectional"))
      (node (ref "C30") (pin "2") (pinfunction "2_2") (pintype "bidirectional"))
      (node (ref "C35") (pin "2") (pinfunction "2_2") (pintype "bidirectional"))
      (node (ref "C9") (pin "2") (pinfunction "2_2") (pintype "bidirectional"))
      (node (ref "DS1") (pin "2") (pinfunction "A_1_2") (pintype "bidirectional"))
      (node (ref "DS1") (pin "5") (pinfunction "A_2_5") (pintype "bidirectional"))
      (node (ref "J2") (pin "22") (pinfunction "22_22") (pintype "bidirectional"))
      (node (ref "J2") (pin "23") (pinfunction "23_23") (pintype "bidirectional"))
      (node (ref "U1") (pin "D1") (pinfunction "VLED_D1") (pintype "bidirectional"))
    )
    (net (code "45") (name "unconnected-(DS1-NC-Pad6)") (class "Default")
      (node (ref "DS1") (pin "6") (pinfunction "NC_6") (pintype "bidirectional"))
    )
    (net (code "46") (name "unconnected-(TP1-TP1-Pad1)") (class "Default")
      (node (ref "TP1") (pin "1") (pinfunction "TP1_1") (pintype "bidirectional"))
    )
    (net (code "47") (name "unconnected-(TP4-TP1-Pad1)") (class "Default")
      (node (ref "TP4") (pin "1") (pinfunction "TP1_1") (pintype "bidirectional"))
    )
    (net (code "48") (name "unconnected-(U1-LED4_DRV-PadF2)") (class "Default")
      (node (ref "U1") (pin "F2") (pinfunction "LED4_DRV_F2") (pintype "bidirectional"))
    )
    (net (code "49") (name "unconnected-(U1-LED5_DRV-PadE3)") (class "Default")
      (node (ref "U1") (pin "E3") (pinfunction "LED5_DRV_E3") (pintype "bidirectional"))
    )
    (net (code "50") (name "unconnected-(U1-LED6_DRV-PadF3)") (class "Default")
      (node (ref "U1") (pin "F3") (pinfunction "LED6_DRV_F3") (pintype "bidirectional"))
    )
    (net (code "51") (name "unconnected-(U1-PD4_IN-PadB2)") (class "Default")
      (node (ref "U1") (pin "B2") (pinfunction "PD4_IN_B2") (pintype "bidirectional"))
    )
    (net (code "52") (name "unconnected-(U20-NC-Pad1)") (class "Default")
      (node (ref "U20") (pin "1") (pinfunction "NC_1") (pintype "bidirectional"))
    )
  )
)
